# rev_l_v8.net
KiCad netlist of a schematic drawn in EAGLE
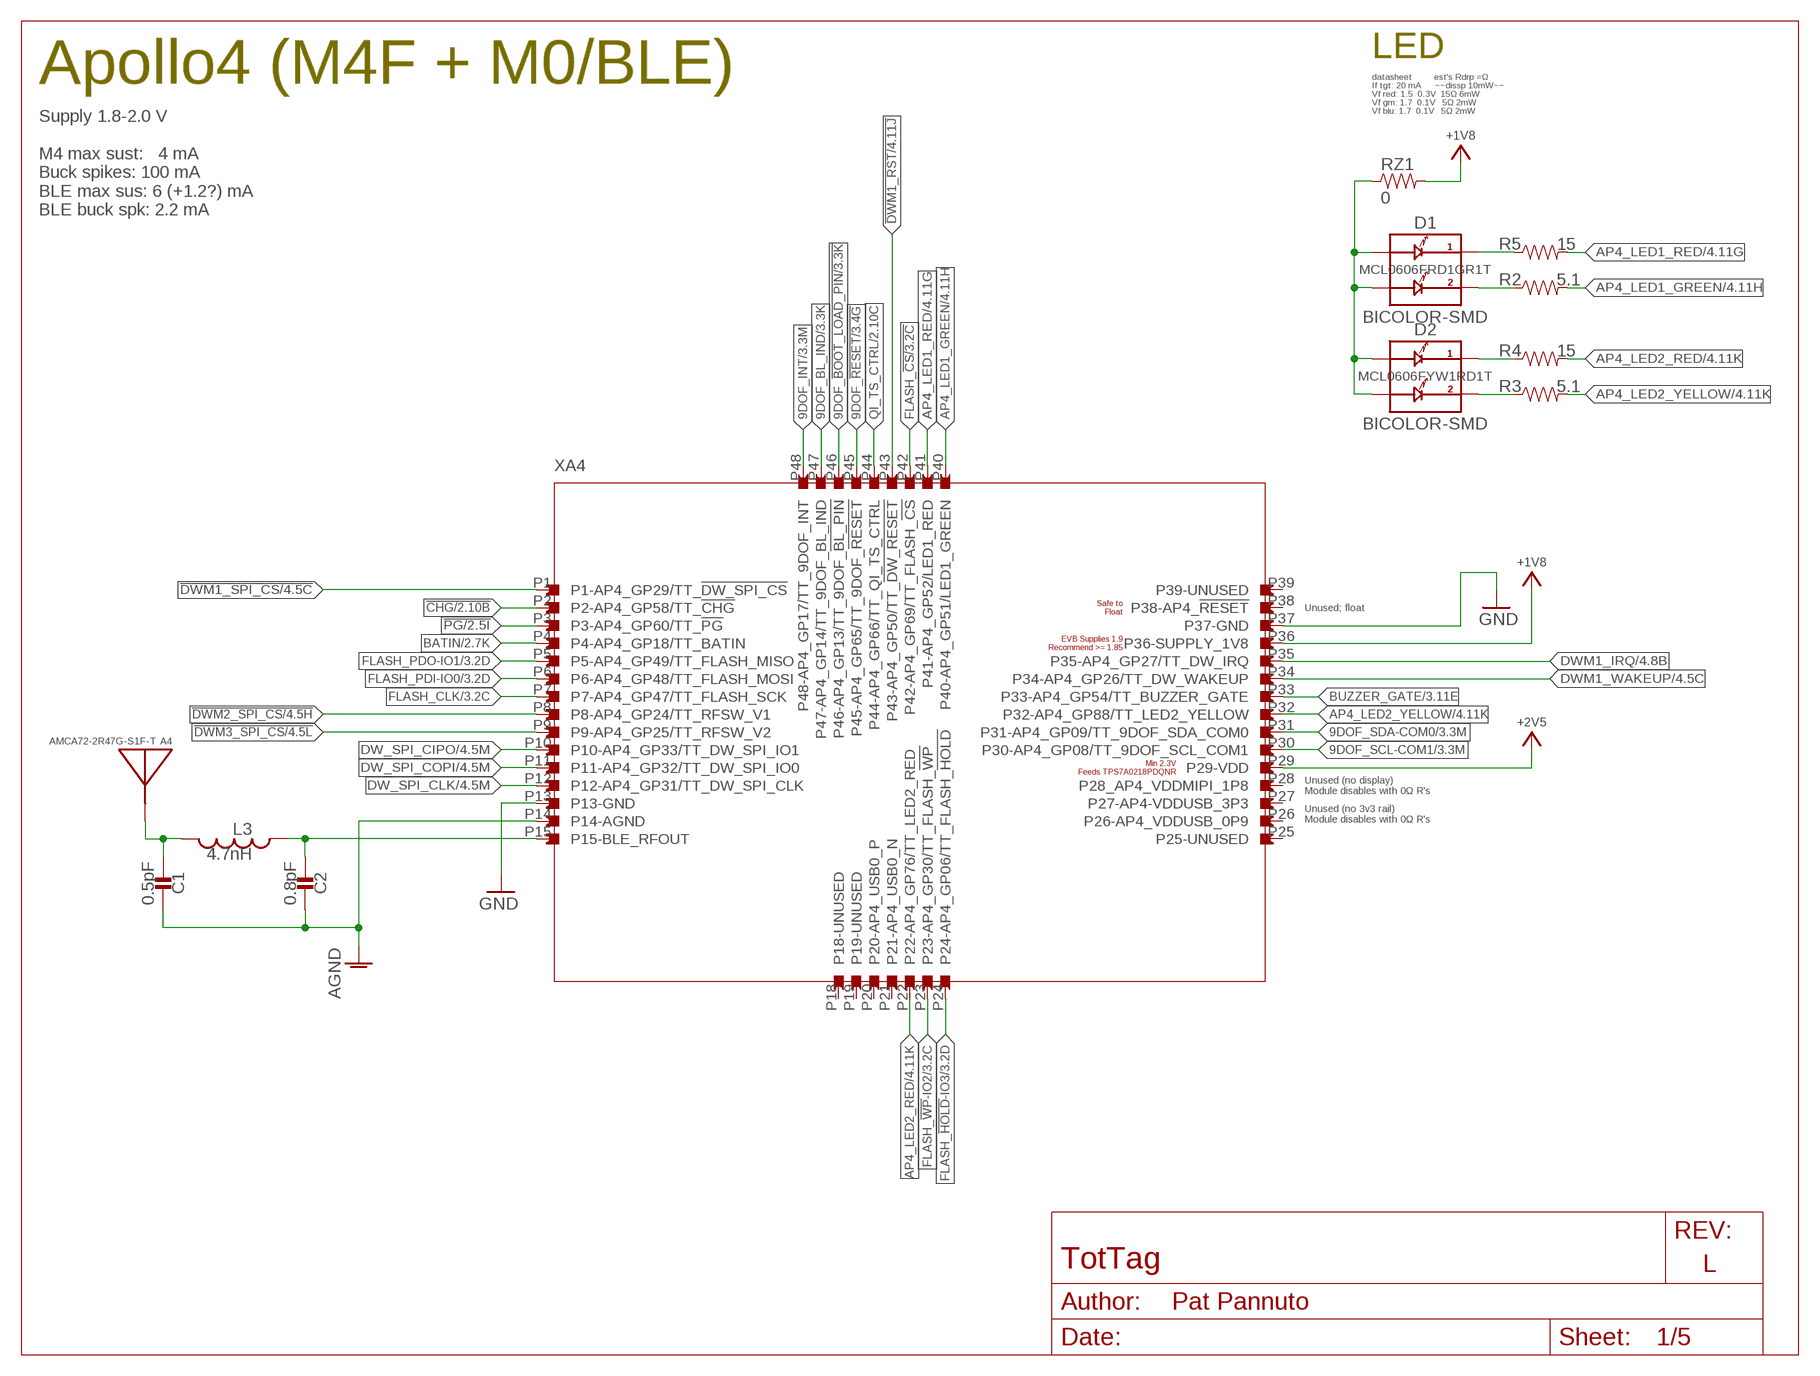
[diagram p0: schematic, sheet 1]
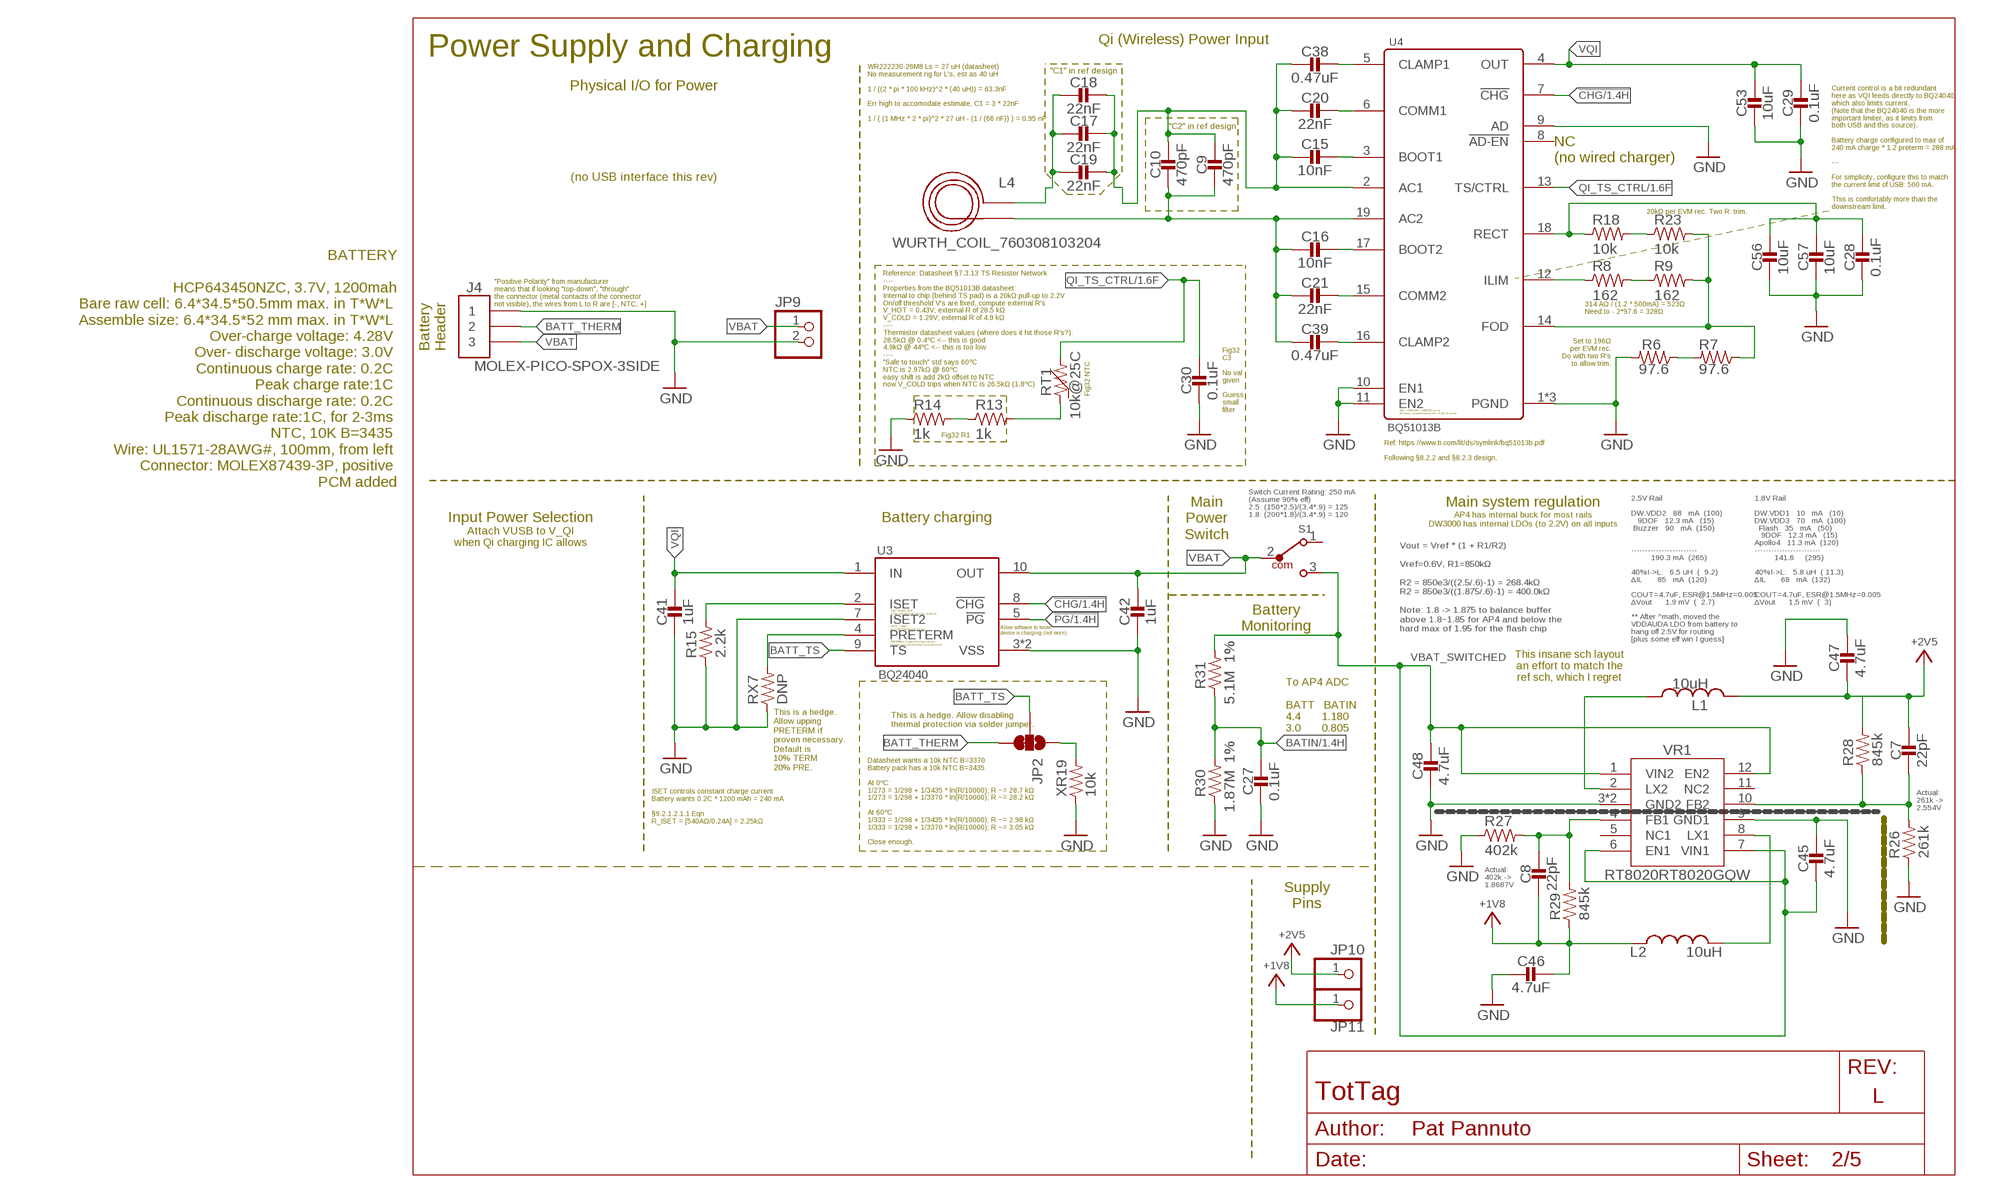
[diagram p1: schematic, sheet 2]
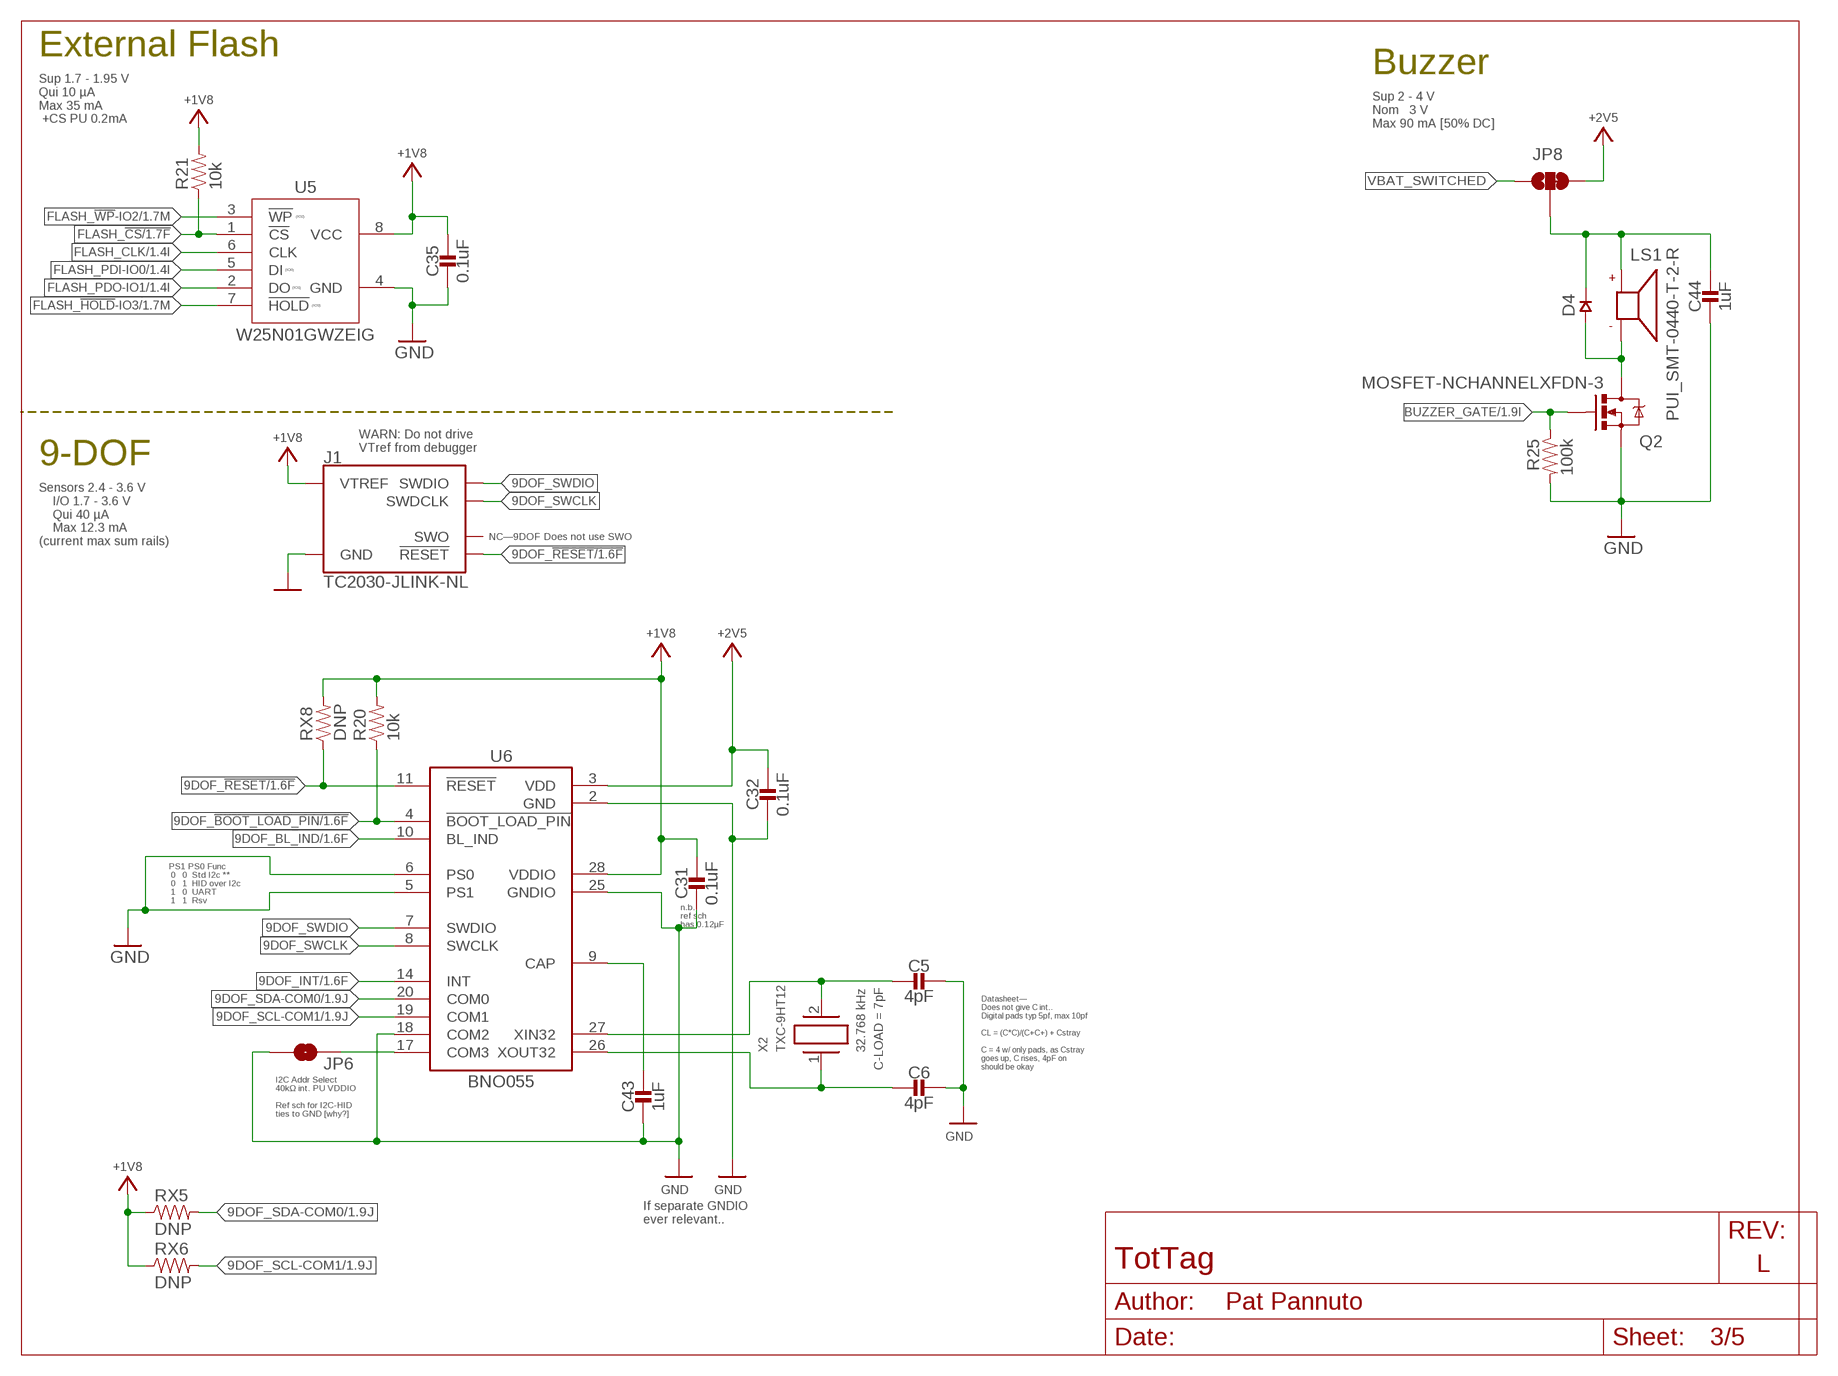
[diagram p2: schematic, sheet 3]
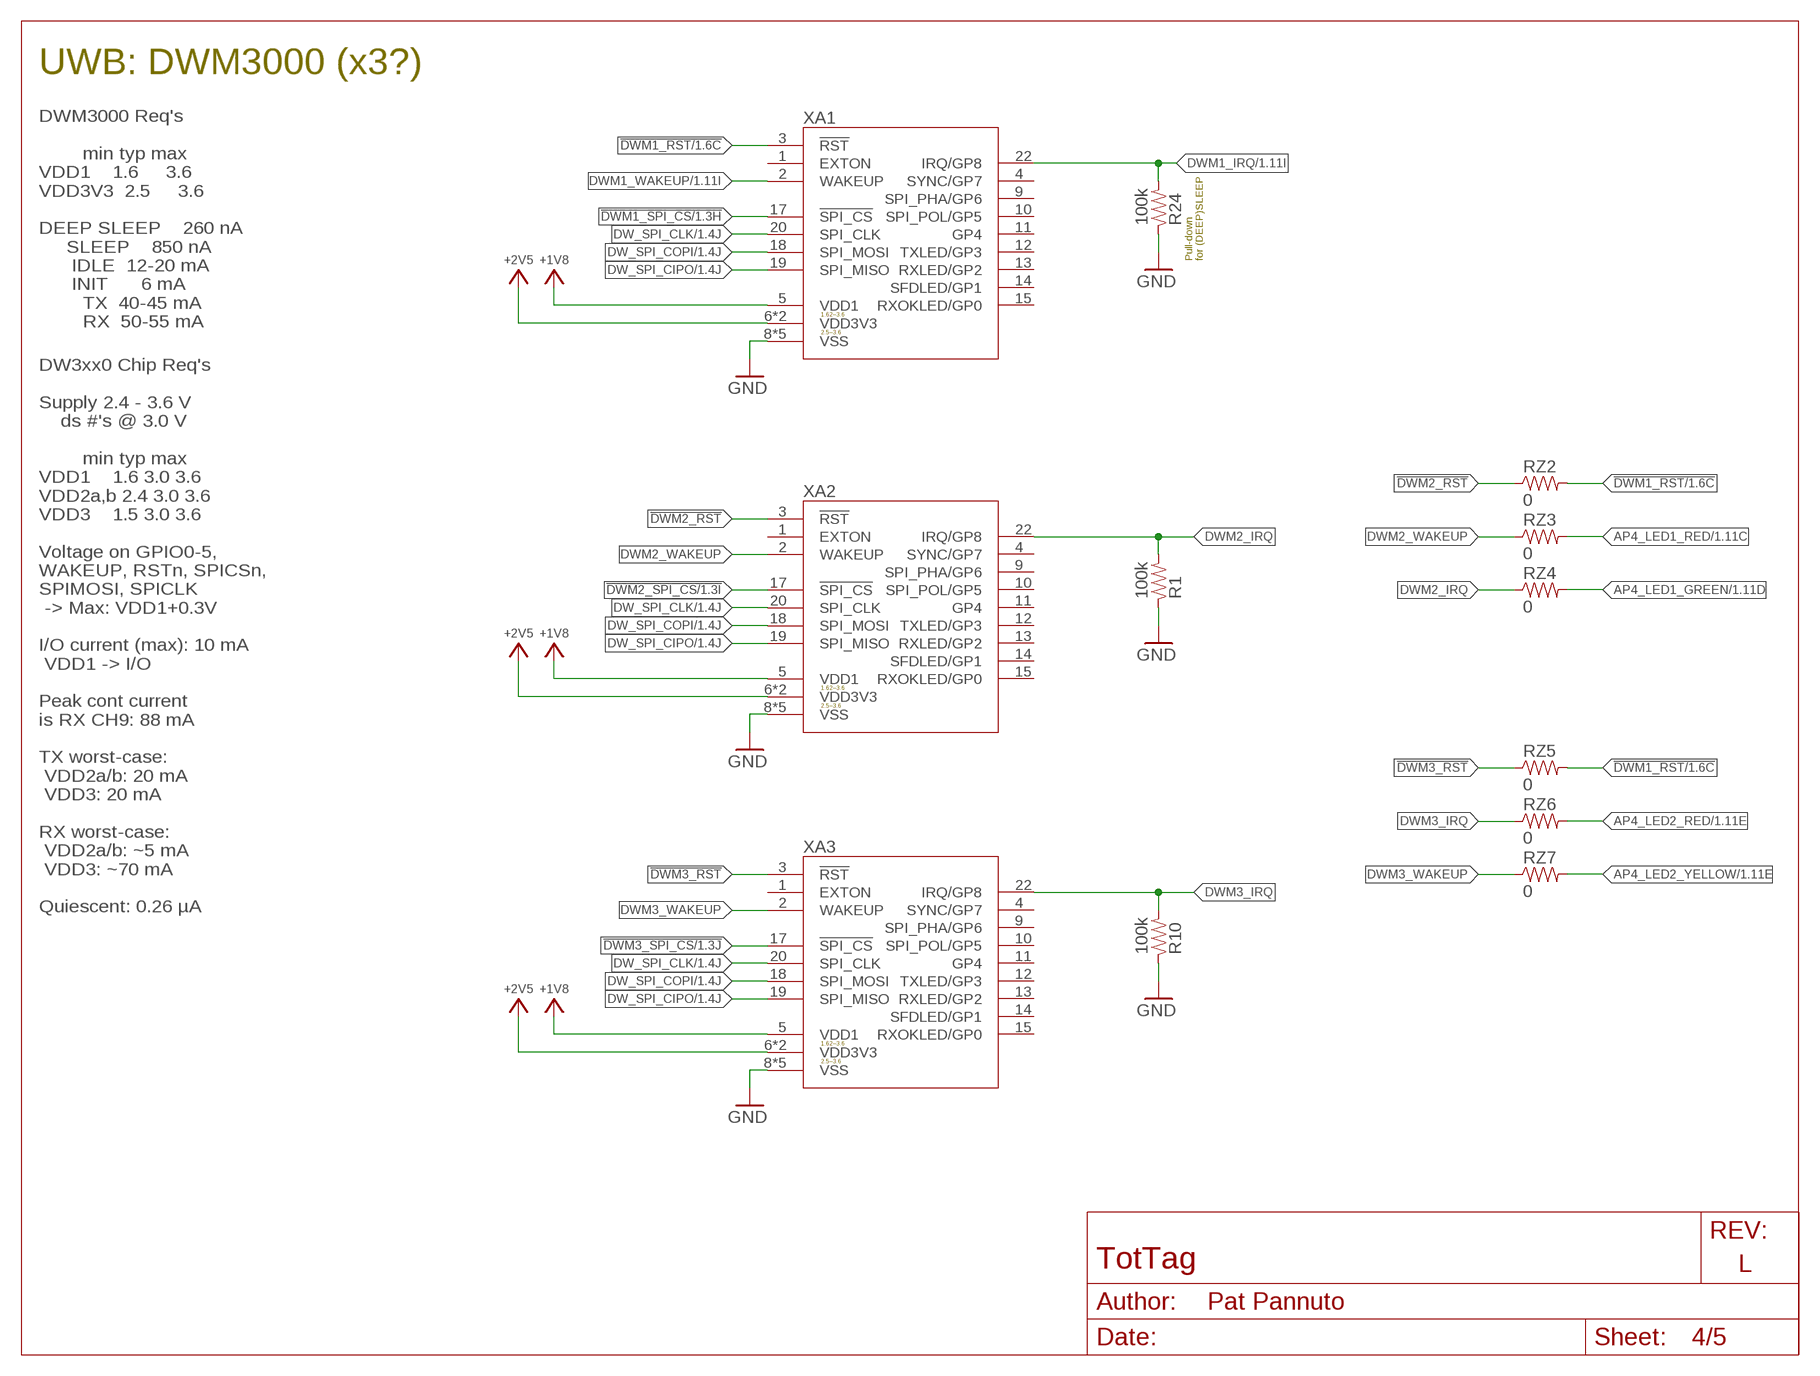
[diagram p3: schematic, sheet 4]
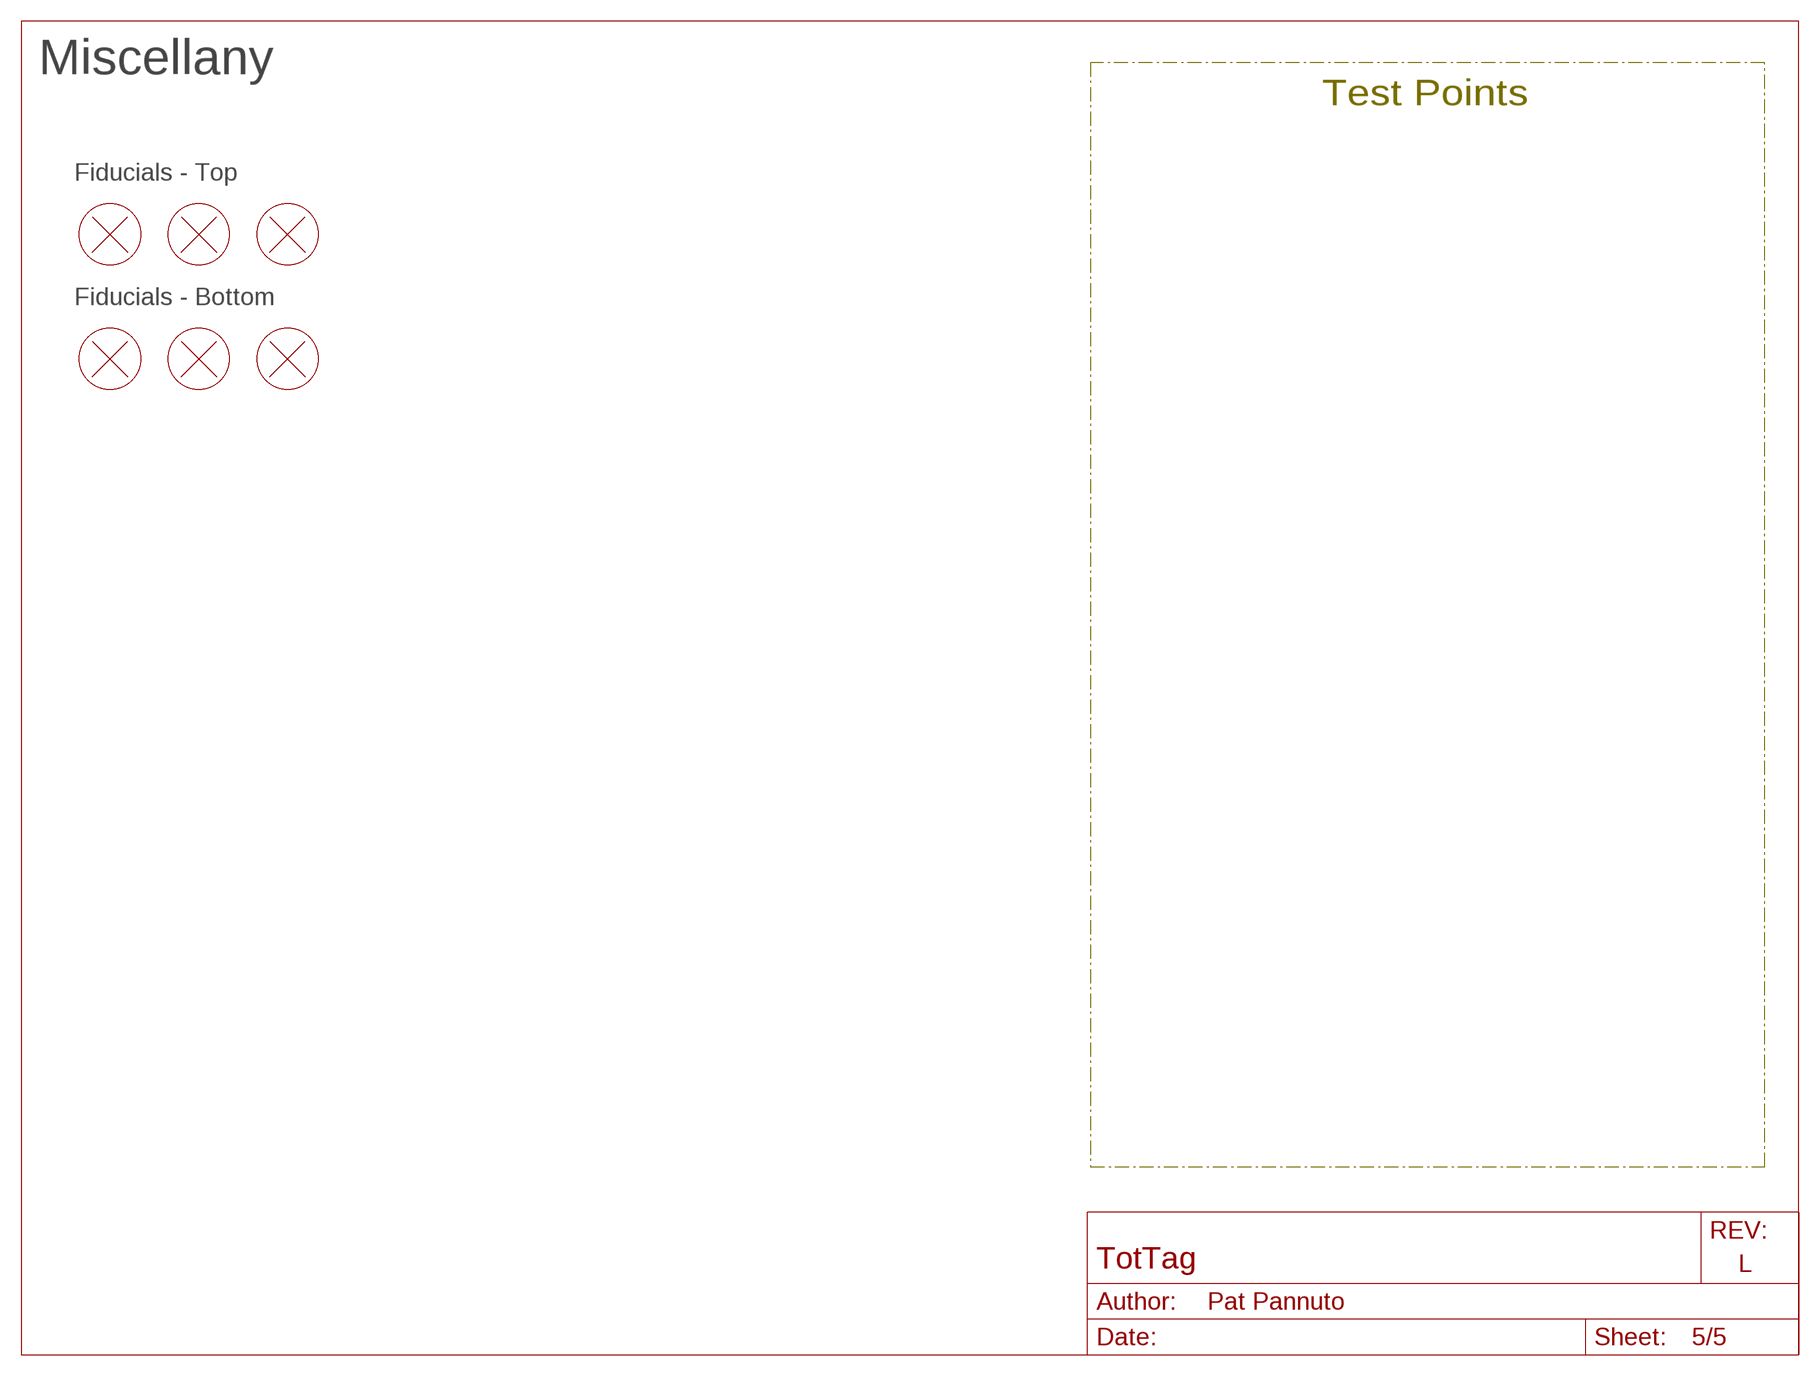
[diagram p4: schematic, sheet 5]

(export (version "E")
  (design (tool "Eeschema 10.0.6"))
  (components
    (comp (ref "R1")
      (value "100k")
      (footprint "eagle-import:0402_RES")
      (fields (field (name "MPN") "RT0402BRE07100KL"))
      (libsource (lib "eagle-import") (part "RESISTOR0402_RES"))
    )
    (comp (ref "R10")
      (value "100k")
      (footprint "eagle-import:0402_RES")
      (fields (field (name "MPN") "RT0402BRE07100KL"))
      (libsource (lib "eagle-import") (part "RESISTOR0402_RES"))
    )
    (comp (ref "R24")
      (value "100k")
      (footprint "eagle-import:0402_RES")
      (fields (field (name "MPN") "RT0402BRE07100KL"))
      (libsource (lib "eagle-import") (part "RESISTOR0402_RES"))
    )
    (comp (ref "RZ2")
      (value "0")
      (footprint "eagle-import:0603-RES")
      (fields (field (name "MPN") "RMCF0603ZT0R00"))
      (libsource (lib "eagle-import") (part "passives_20904581_RESISTOR0603_RES"))
    )
    (comp (ref "RZ3")
      (value "0")
      (footprint "eagle-import:0603-RES")
      (fields (field (name "MPN") "RMCF0603ZT0R00"))
      (libsource (lib "eagle-import") (part "passives_20904581_RESISTOR0603_RES"))
    )
    (comp (ref "RZ4")
      (value "0")
      (footprint "eagle-import:0603-RES")
      (fields (field (name "MPN") "RMCF0603ZT0R00"))
      (libsource (lib "eagle-import") (part "passives_20904581_RESISTOR0603_RES"))
    )
    (comp (ref "RZ5")
      (value "0")
      (footprint "eagle-import:0603-RES")
      (fields (field (name "MPN") "RMCF0603ZT0R00"))
      (libsource (lib "eagle-import") (part "passives_20904581_RESISTOR0603_RES"))
    )
    (comp (ref "RZ6")
      (value "0")
      (footprint "eagle-import:0603-RES")
      (fields (field (name "MPN") "RMCF0603ZT0R00"))
      (libsource (lib "eagle-import") (part "passives_20904581_RESISTOR0603_RES"))
    )
    (comp (ref "RZ7")
      (value "0")
      (footprint "eagle-import:0603-RES")
      (fields (field (name "MPN") "RMCF0603ZT0R00"))
      (libsource (lib "eagle-import") (part "passives_20904581_RESISTOR0603_RES"))
    )
    (comp (ref "XA1")
      (value "DWM3000")
      (footprint "eagle-import:DWM3000")
      (libsource (lib "eagle-import") (part "DWM3000"))
    )
    (comp (ref "XA2")
      (value "DWM3000")
      (footprint "eagle-import:DWM3000")
      (libsource (lib "eagle-import") (part "DWM3000"))
    )
    (comp (ref "XA3")
      (value "DWM3000")
      (footprint "eagle-import:DWM3000")
      (libsource (lib "eagle-import") (part "DWM3000"))
    )
    (comp (ref "C5")
      (value "4pF")
      (footprint "eagle-import:0201_CAP")
      (fields (field (name "MANUFACTURER") "Murata") (field (name "MPN") "GRM0335C1H4R0BA01D"))
      (libsource (lib "eagle-import") (part "passives_20904581_CAPACITOR0201_CAP"))
    )
    (comp (ref "C6")
      (value "4pF")
      (footprint "eagle-import:0201_CAP")
      (fields (field (name "MANUFACTURER") "Murata") (field (name "MPN") "GRM0335C1H4R0BA01D"))
      (libsource (lib "eagle-import") (part "passives_20904581_CAPACITOR0201_CAP"))
    )
    (comp (ref "C31")
      (value "0.1uF")
      (footprint "eagle-import:0402_CAP")
      (fields (field (name "MPN") "CL05A104KP5NNNC"))
      (libsource (lib "eagle-import") (part "passives_20904581_CAPACITOR0402_CAP"))
    )
    (comp (ref "C32")
      (value "0.1uF")
      (footprint "eagle-import:0402_CAP")
      (fields (field (name "MPN") "CL05A104KP5NNNC"))
      (libsource (lib "eagle-import") (part "passives_20904581_CAPACITOR0402_CAP"))
    )
    (comp (ref "C35")
      (value "0.1uF")
      (footprint "eagle-import:0402_CAP")
      (fields (field (name "MPN") "CL05A104KP5NNNC"))
      (libsource (lib "eagle-import") (part "passives_20904581_CAPACITOR0402_CAP"))
    )
    (comp (ref "C43")
      (value "1uF")
      (footprint "eagle-import:0402_CAP")
      (fields (field (name "MPN") "GRM155R70J105KA12J"))
      (libsource (lib "eagle-import") (part "CAPACITOR0402_CAP"))
    )
    (comp (ref "C44")
      (value "1uF")
      (footprint "eagle-import:0402_CAP")
      (fields (field (name "MPN") "GRM155R70J105KA12J"))
      (libsource (lib "eagle-import") (part "CAPACITOR0402_CAP"))
    )
    (comp (ref "D4")
      (value "DIODE0402")
      (footprint "eagle-import:0402_DIODE")
      (fields (field (name "MPN") "CDSQR400B-HF"))
      (libsource (lib "eagle-import") (part "DIODE0402"))
    )
    (comp (ref "J1")
      (value "TC2030-JLINK-NL")
      (footprint "eagle-import:TC2030-IDC-NL")
      (libsource (lib "eagle-import") (part "TC2030-JLINK-NL"))
    )
    (comp (ref "JP6")
      (value "JUMPER-SMT_2_NO_SILK")
      (footprint "eagle-import:SMT-JUMPER_2_NO_SILK")
      (libsource (lib "eagle-import") (part "JUMPER-SMT_2_NO_SILK"))
    )
    (comp (ref "JP8")
      (value "JUMPER-SMT_3_1-NC_TRACE_SILK")
      (footprint "eagle-import:SMT-JUMPER_3_1-NC_TRACE_SILK")
      (libsource (lib "eagle-import") (part "JUMPER-SMT_3_1-NC_TRACE_SILK"))
    )
    (comp (ref "LS1")
      (value "PUI_SMT-0440-T-2-R")
      (footprint "eagle-import:SMT-0440-T-2-R")
      (fields (field (name "MPN") "SMT-0440-T-2-R"))
      (libsource (lib "eagle-import") (part "PUI_SMT-0440-T-2-R"))
    )
    (comp (ref "Q2")
      (value "MOSFET-NCHANNELXFDN-3")
      (footprint "eagle-import:XFDFN-3")
      (libsource (lib "eagle-import") (part "MOSFET-NCHANNELXFDN-3"))
    )
    (comp (ref "R20")
      (value "10k")
      (footprint "eagle-import:0402_RES")
      (fields (field (name "MPN") "RC0402JR-0710KL"))
      (libsource (lib "eagle-import") (part "RESISTOR0402_RES"))
    )
    (comp (ref "R21")
      (value "10k")
      (footprint "eagle-import:0402_RES")
      (fields (field (name "MPN") "RC0402JR-0710KL"))
      (libsource (lib "eagle-import") (part "RESISTOR0402_RES"))
    )
    (comp (ref "R25")
      (value "100k")
      (footprint "eagle-import:0402_RES")
      (fields (field (name "MPN") "RT0402BRE07100KL"))
      (libsource (lib "eagle-import") (part "RESISTOR0402_RES"))
    )
    (comp (ref "RX5")
      (value "DNP")
      (footprint "eagle-import:0603-RES")
      (libsource (lib "eagle-import") (part "passives_20904581_RESISTOR0603_RES"))
    )
    (comp (ref "RX6")
      (value "DNP")
      (footprint "eagle-import:0603-RES")
      (libsource (lib "eagle-import") (part "passives_20904581_RESISTOR0603_RES"))
    )
    (comp (ref "RX8")
      (value "DNP")
      (footprint "eagle-import:0603-RES")
      (libsource (lib "eagle-import") (part "passives_20904581_RESISTOR0603_RES"))
    )
    (comp (ref "U5")
      (value "W25N01GWZEIG")
      (footprint "eagle-import:WSON127P800X600X80-9T430X340N")
      (fields (field (name "MANUFACTURER") "Winbond"))
      (libsource (lib "eagle-import") (part "W25N01GWZEIG"))
    )
    (comp (ref "U6")
      (value "BNO055")
      (footprint "eagle-import:LGA28R0P510X4_5P2X3P8X1")
      (fields (field (name "MANUFACTURER") "Bosch Scientific"))
      (libsource (lib "eagle-import") (part "BNO055"))
    )
    (comp (ref "X2")
      (value "TXC-9HT12")
      (footprint "eagle-import:TXC-9HT12")
      (fields
        (field (name "C-LOAD") "7pF")
        (field (name "FREQUENCY") "32.768 kHz")
        (field (name "MANUFACTURER") "TXC Corp")
        (field (name "MPN") "9HT12-32.768KDZY-T")
      )
      (libsource (lib "eagle-import") (part "TXC-9HT12"))
    )
    (comp (ref "C7")
      (value "22pF")
      (footprint "eagle-import:0201_CAP")
      (fields (field (name "MPN") "GRM0335C1H220FA01D"))
      (libsource (lib "eagle-import") (part "passives_20904581_CAPACITOR0201_CAP"))
    )
    (comp (ref "C8")
      (value "22pF")
      (footprint "eagle-import:0201_CAP")
      (fields (field (name "MPN") "GRM0335C1H220FA01D"))
      (libsource (lib "eagle-import") (part "passives_20904581_CAPACITOR0201_CAP"))
    )
    (comp (ref "C9")
      (value "470pF")
      (footprint "eagle-import:0402_CAP")
      (description "CAP CER 470PF 50V C0G/NP0 0402")
      (fields (field (name "MANUFACTURER") "Murata") (field (name "MPN") "GRM1555C1H471JA01J"))
      (libsource (lib "eagle-import") (part "passives_20904581_CAPACITOR0402_CAP"))
    )
    (comp (ref "C10")
      (value "470pF")
      (footprint "eagle-import:0402_CAP")
      (description "CAP CER 470PF 50V C0G/NP0 0402")
      (fields (field (name "MANUFACTURER") "Murata") (field (name "MPN") "GRM1555C1H471JA01J"))
      (libsource (lib "eagle-import") (part "passives_20904581_CAPACITOR0402_CAP"))
    )
    (comp (ref "C15")
      (value "10nF")
      (footprint "eagle-import:0402_CAP")
      (fields (field (name "MPN") "GRM155R71H103KA88J"))
      (libsource (lib "eagle-import") (part "passives_20904581_CAPACITOR0402_CAP"))
    )
    (comp (ref "C16")
      (value "10nF")
      (footprint "eagle-import:0402_CAP")
      (fields (field (name "MPN") "GRM155R71H103KA88J"))
      (libsource (lib "eagle-import") (part "passives_20904581_CAPACITOR0402_CAP"))
    )
    (comp (ref "C17")
      (value "22nF")
      (footprint "eagle-import:0402_CAP")
      (fields (field (name "MPN") "GRM155R71E223JA61D"))
      (libsource (lib "eagle-import") (part "passives_20904581_CAPACITOR0402_CAP"))
    )
    (comp (ref "C18")
      (value "22nF")
      (footprint "eagle-import:0402_CAP")
      (fields (field (name "MPN") "GRM155R71E223JA61D"))
      (libsource (lib "eagle-import") (part "passives_20904581_CAPACITOR0402_CAP"))
    )
    (comp (ref "C19")
      (value "22nF")
      (footprint "eagle-import:0402_CAP")
      (fields (field (name "MPN") "GRM155R71E223JA61D"))
      (libsource (lib "eagle-import") (part "passives_20904581_CAPACITOR0402_CAP"))
    )
    (comp (ref "C20")
      (value "22nF")
      (footprint "eagle-import:0402_CAP")
      (fields (field (name "MPN") "CC0402ZRY5V8BB223"))
      (libsource (lib "eagle-import") (part "passives_20904581_CAPACITOR0402_CAP"))
    )
    (comp (ref "C21")
      (value "22nF")
      (footprint "eagle-import:0402_CAP")
      (fields (field (name "MPN") "CC0402ZRY5V8BB223"))
      (libsource (lib "eagle-import") (part "passives_20904581_CAPACITOR0402_CAP"))
    )
    (comp (ref "C27")
      (value "0.1uF")
      (footprint "eagle-import:0402_CAP")
      (fields (field (name "MPN") "GRM155R71C104KA88J "))
      (libsource (lib "eagle-import") (part "CAPACITOR0402_CAP"))
    )
    (comp (ref "C28")
      (value "0.1uF")
      (footprint "eagle-import:0402_CAP")
      (fields (field (name "MPN") "GRM155R71C104KA88J "))
      (libsource (lib "eagle-import") (part "CAPACITOR0402_CAP"))
    )
    (comp (ref "C29")
      (value "0.1uF")
      (footprint "eagle-import:0402_CAP")
      (fields (field (name "MPN") "GRM155R71C104KA88J "))
      (libsource (lib "eagle-import") (part "CAPACITOR0402_CAP"))
    )
    (comp (ref "C30")
      (value "0.1uF")
      (footprint "eagle-import:0402_CAP")
      (fields (field (name "MPN") "GRM155R71C104KA88J "))
      (libsource (lib "eagle-import") (part "CAPACITOR0402_CAP"))
    )
    (comp (ref "C38")
      (value "0.47uF")
      (footprint "eagle-import:0402_CAP")
      (fields (field (name "MPN") "GRT155R61E474ME01D"))
      (libsource (lib "eagle-import") (part "passives_20904581_CAPACITOR0402_CAP"))
    )
    (comp (ref "C39")
      (value "0.47uF")
      (footprint "eagle-import:0402_CAP")
      (fields (field (name "MPN") "GRT155R61E474ME01D"))
      (libsource (lib "eagle-import") (part "passives_20904581_CAPACITOR0402_CAP"))
    )
    (comp (ref "C41")
      (value "1uF")
      (footprint "eagle-import:0402_CAP")
      (fields (field (name "MPN") "GRM155R70J105KA12J"))
      (libsource (lib "eagle-import") (part "CAPACITOR0402_CAP"))
    )
    (comp (ref "C42")
      (value "1uF")
      (footprint "eagle-import:0402_CAP")
      (fields (field (name "MPN") "GRM155R70J105KA12J"))
      (libsource (lib "eagle-import") (part "CAPACITOR0402_CAP"))
    )
    (comp (ref "C45")
      (value "4.7uF")
      (footprint "eagle-import:0603_CAP")
      (fields (field (name "MPN") "C1608X7S1A475K080AC"))
      (libsource (lib "eagle-import") (part "passives_20904581_CAPACITOR0603_CAP"))
    )
    (comp (ref "C46")
      (value "4.7uF")
      (footprint "eagle-import:0603_CAP")
      (fields (field (name "MPN") "C1608X7S1A475K080AC"))
      (libsource (lib "eagle-import") (part "passives_20904581_CAPACITOR0603_CAP"))
    )
    (comp (ref "C47")
      (value "4.7uF")
      (footprint "eagle-import:0603_CAP")
      (fields (field (name "MPN") "C1608X7S1A475K080AC"))
      (libsource (lib "eagle-import") (part "passives_20904581_CAPACITOR0603_CAP"))
    )
    (comp (ref "C48")
      (value "4.7uF")
      (footprint "eagle-import:0603_CAP")
      (fields (field (name "MPN") "C1608X7S1A475K080AC"))
      (libsource (lib "eagle-import") (part "passives_20904581_CAPACITOR0603_CAP"))
    )
    (comp (ref "C53")
      (value "10uF")
      (footprint "eagle-import:0603_CAP")
      (fields (field (name "MPN") "CM105X5R106M25AT"))
      (libsource (lib "eagle-import") (part "passives_20904581_CAPACITOR0603_CAP"))
    )
    (comp (ref "C56")
      (value "10uF")
      (footprint "eagle-import:0603_CAP")
      (fields (field (name "MPN") "CM105X5R106M25AT"))
      (libsource (lib "eagle-import") (part "passives_20904581_CAPACITOR0603_CAP"))
    )
    (comp (ref "C57")
      (value "10uF")
      (footprint "eagle-import:0603_CAP")
      (fields (field (name "MPN") "CM105X5R106M25AT"))
      (libsource (lib "eagle-import") (part "passives_20904581_CAPACITOR0603_CAP"))
    )
    (comp (ref "J4")
      (value "MOLEX-PICO-SPOX-3SIDE")
      (footprint "eagle-import:MOLEX-PICO-SPOX-3_SIDE")
      (libsource (lib "eagle-import") (part "MOLEX-PICO-SPOX-3SIDE"))
    )
    (comp (ref "JP2")
      (value "JUMPER-SMT_3_1-NC_TRACE_SILK")
      (footprint "eagle-import:SMT-JUMPER_3_1-NC_TRACE_SILK")
      (libsource (lib "eagle-import") (part "JUMPER-SMT_3_1-NC_TRACE_SILK"))
    )
    (comp (ref "JP9")
      (value "PINHD-1X2")
      (footprint "eagle-import:1X02")
      (libsource (lib "eagle-import") (part "PINHD-1X2"))
    )
    (comp (ref "JP10")
      (value "PINHD-1X1")
      (footprint "eagle-import:1X01")
      (libsource (lib "eagle-import") (part "PINHD-1X1"))
    )
    (comp (ref "JP11")
      (value "PINHD-1X1")
      (footprint "eagle-import:1X01")
      (libsource (lib "eagle-import") (part "PINHD-1X1"))
    )
    (comp (ref "L1")
      (value "10uH")
      (footprint "eagle-import:NRX3015")
      (fields (field (name "MANUFACTURER") "TAIYO YUDEN") (field (name "MPN") "NR3015T100M"))
      (libsource (lib "eagle-import") (part "INDUCTORNRX3015"))
    )
    (comp (ref "L2")
      (value "10uH")
      (footprint "eagle-import:NRX3015")
      (fields (field (name "MANUFACTURER") "TAIYO YUDEN") (field (name "MPN") "NR3015T100M"))
      (libsource (lib "eagle-import") (part "INDUCTORNRX3015"))
    )
    (comp (ref "L4")
      (value "WURTH_COIL_760308103204")
      (footprint "eagle-import:WURTH_COIL_760308103204")
      (fields (field (name "MANUFACTURER") "Würth Elektronik") (field (name "MPN") "760308103204"))
      (libsource (lib "eagle-import") (part "WURTH_COIL_760308103204"))
    )
    (comp (ref "R6")
      (value "97.6")
      (footprint "eagle-import:0402_RES")
      (fields (field (name "MPN") "RMCF0402FT97R6"))
      (libsource (lib "eagle-import") (part "passives_20904581_RESISTOR0402_RES"))
    )
    (comp (ref "R7")
      (value "97.6")
      (footprint "eagle-import:0402_RES")
      (fields (field (name "MPN") "RMCF0402FT97R6"))
      (libsource (lib "eagle-import") (part "passives_20904581_RESISTOR0402_RES"))
    )
    (comp (ref "R8")
      (value "162")
      (footprint "eagle-import:0402_RES")
      (fields (field (name "MPN") "RMCF0402FT162R"))
      (libsource (lib "eagle-import") (part "passives_20904581_RESISTOR0402_RES"))
    )
    (comp (ref "R9")
      (value "162")
      (footprint "eagle-import:0402_RES")
      (fields (field (name "MPN") "RMCF0402FT162R"))
      (libsource (lib "eagle-import") (part "passives_20904581_RESISTOR0402_RES"))
    )
    (comp (ref "R13")
      (value "1k")
      (footprint "eagle-import:0402_RES")
      (libsource (lib "eagle-import") (part "RESISTOR0402_RES"))
    )
    (comp (ref "R14")
      (value "1k")
      (footprint "eagle-import:0402_RES")
      (libsource (lib "eagle-import") (part "RESISTOR0402_RES"))
    )
    (comp (ref "R15")
      (value "2.2k")
      (footprint "eagle-import:0402_RES")
      (fields (field (name "MPN") "RMCF0402JT2K20"))
      (libsource (lib "eagle-import") (part "passives_20904581_RESISTOR0402_RES"))
    )
    (comp (ref "R18")
      (value "10k")
      (footprint "eagle-import:0402_RES")
      (fields (field (name "MPN") "RC0402JR-0710KL"))
      (libsource (lib "eagle-import") (part "RESISTOR0402_RES"))
    )
    (comp (ref "R23")
      (value "10k")
      (footprint "eagle-import:0402_RES")
      (fields (field (name "MPN") "RC0402JR-0710KL"))
      (libsource (lib "eagle-import") (part "RESISTOR0402_RES"))
    )
    (comp (ref "R26")
      (value "261k")
      (footprint "eagle-import:0201_RES")
      (fields (field (name "MPN") "ERJ-1GNF2613C"))
      (libsource (lib "eagle-import") (part "passives_20904581_RESISTOR0201_RES"))
    )
    (comp (ref "R27")
      (value "402k")
      (footprint "eagle-import:0201_RES")
      (fields (field (name "MPN") "ERJ-1GNF4023C"))
      (libsource (lib "eagle-import") (part "passives_20904581_RESISTOR0201_RES"))
    )
    (comp (ref "R28")
      (value "845k")
      (footprint "eagle-import:0201_RES")
      (fields (field (name "MPN") "ERJ-1GNF8453C"))
      (libsource (lib "eagle-import") (part "passives_20904581_RESISTOR0201_RES"))
    )
    (comp (ref "R29")
      (value "845k")
      (footprint "eagle-import:0201_RES")
      (fields (field (name "MPN") "ERJ-1GNF8453C"))
      (libsource (lib "eagle-import") (part "passives_20904581_RESISTOR0201_RES"))
    )
    (comp (ref "R30")
      (value "1.87M")
      (footprint "eagle-import:0402_RES")
      (fields (field (name "MPN") "RMCF0402FT1M87") (field (name "TOLERANCE") "1%"))
      (libsource (lib "eagle-import") (part "RESISTOR0402_RES"))
    )
    (comp (ref "R31")
      (value "5.1M")
      (footprint "eagle-import:0402_RES")
      (fields (field (name "MPN") "RMCF0402FT5M10") (field (name "TOLERANCE") "1%"))
      (libsource (lib "eagle-import") (part "RESISTOR0402_RES"))
    )
    (comp (ref "RT1")
      (value "10k@25C")
      (footprint "eagle-import:0402_RES")
      (fields (field (name "MPN") "NCU15XH103F60RC"))
      (libsource (lib "eagle-import") (part "THERMISTOR0402"))
    )
    (comp (ref "RX7")
      (value "DNP")
      (footprint "eagle-import:0402_RES")
      (libsource (lib "eagle-import") (part "passives_20904581_RESISTOR0402_RES"))
    )
    (comp (ref "S1")
      (value "450404015514")
      (footprint "eagle-import:450404015514")
      (libsource (lib "eagle-import") (part "450404015514"))
    )
    (comp (ref "U3")
      (value "BQ24040")
      (footprint "eagle-import:DSQ0010A")
      (fields (field (name "MPN") "BQ24040DSQR"))
      (libsource (lib "eagle-import") (part "BQ24040"))
    )
    (comp (ref "U4")
      (value "BQ51013B")
      (footprint "eagle-import:RHL0020A")
      (fields (field (name "MPN") "BQ51013BRHLR"))
      (libsource (lib "eagle-import") (part "BQ51013B"))
    )
    (comp (ref "VR1")
      (value "RT8020RT8020GQW")
      (footprint "eagle-import:SON45P300X300X80-13T160X250N")
      (fields (field (name "MANUFACTURER") "RichTek") (field (name "MPN") "RT8020GQW"))
      (libsource (lib "eagle-import") (part "RT8020RT8020GQW"))
    )
    (comp (ref "XR19")
      (value "10k")
      (footprint "eagle-import:0402_RES")
      (fields (field (name "MPN") "RC0402JR-0710KL"))
      (libsource (lib "eagle-import") (part "RESISTOR0402_RES"))
    )
    (comp (ref "A4")
      (value "AMCA72-2R47G-S1F-T")
      (footprint "eagle-import:AMCA72-2R470G-S1F-T")
      (fields (field (name "MPN") "AMCA72-2R470G-S1F-T4"))
      (libsource (lib "eagle-import") (part "AMCA72-2R47G-S1F-T"))
    )
    (comp (ref "C1")
      (value "0.5pF")
      (footprint "eagle-import:0402_CAP")
      (fields (field (name "MPN") "GJM1555C1HR50WB01D"))
      (libsource (lib "eagle-import") (part "CAPACITOR0402_CAP"))
    )
    (comp (ref "C2")
      (value "0.8pF")
      (footprint "eagle-import:0402_CAP")
      (fields (field (name "MPN") "GJM1555C1HR80WB01D"))
      (libsource (lib "eagle-import") (part "CAPACITOR0402_CAP"))
    )
    (comp (ref "D1")
      (value "BICOLOR-SMD")
      (footprint "eagle-import:LED-0606")
      (fields (field (name "MPN") "MCL0606FRD1GR1T"))
      (libsource (lib "eagle-import") (part "BICOLOR-SMD"))
    )
    (comp (ref "D2")
      (value "BICOLOR-SMD")
      (footprint "eagle-import:LED-0606")
      (fields (field (name "MPN") "MCL0606FYW1RD1T"))
      (libsource (lib "eagle-import") (part "BICOLOR-SMD"))
    )
    (comp (ref "L3")
      (value "4.7nH")
      (footprint "eagle-import:0402_CAP")
      (fields (field (name "MPN") "LQW15AN4N7G8ZD"))
      (libsource (lib "eagle-import") (part "INDUCTOR0402"))
    )
    (comp (ref "R2")
      (value "5.1")
      (footprint "eagle-import:0402_RES")
      (fields (field (name "MPN") "RC0402JR-075R1L"))
      (libsource (lib "eagle-import") (part "RESISTOR0402_RES"))
    )
    (comp (ref "R3")
      (value "5.1")
      (footprint "eagle-import:0402_RES")
      (fields (field (name "MPN") "RC0402JR-075R1L"))
      (libsource (lib "eagle-import") (part "RESISTOR0402_RES"))
    )
    (comp (ref "R4")
      (value "15")
      (footprint "eagle-import:0402_RES")
      (fields (field (name "MPN") "RC0402JR-0715RL"))
      (libsource (lib "eagle-import") (part "RESISTOR0402_RES"))
    )
    (comp (ref "R5")
      (value "15")
      (footprint "eagle-import:0402_RES")
      (fields (field (name "MPN") "RC0402JR-0715RL"))
      (libsource (lib "eagle-import") (part "RESISTOR0402_RES"))
    )
    (comp (ref "RZ1")
      (value "0")
      (footprint "eagle-import:0603-RES")
      (fields (field (name "MPN") "RMCF0603ZT0R00"))
      (libsource (lib "eagle-import") (part "passives_20904581_RESISTOR0603_RES"))
    )
    (comp (ref "XA4")
      (value "APOLLO4_BLUEPLUS_MODULE")
      (footprint "eagle-import:APOLLO4_BLUEPLUS_MODULE")
      (libsource (lib "eagle-import") (part "APOLLO4_BLUEPLUS_MODULE"))
    )
    (comp (ref "FD1")
      (value "FIDUCIAL")
      (footprint "eagle-import:FIDUCIAL_1MM-CU_2MM-MASK")
      (libsource (lib "eagle-import") (part "FIDUCIAL"))
    )
    (comp (ref "FD2")
      (value "FIDUCIAL")
      (footprint "eagle-import:FIDUCIAL_1MM-CU_2MM-MASK")
      (libsource (lib "eagle-import") (part "FIDUCIAL"))
    )
    (comp (ref "FD3")
      (value "FIDUCIAL")
      (footprint "eagle-import:FIDUCIAL_1MM-CU_2MM-MASK")
      (libsource (lib "eagle-import") (part "FIDUCIAL"))
    )
    (comp (ref "FD4")
      (value "FIDUCIAL")
      (footprint "eagle-import:FIDUCIAL_1MM-CU_2MM-MASK")
      (libsource (lib "eagle-import") (part "FIDUCIAL"))
    )
    (comp (ref "FD5")
      (value "FIDUCIAL")
      (footprint "eagle-import:FIDUCIAL_1MM-CU_2MM-MASK")
      (libsource (lib "eagle-import") (part "FIDUCIAL"))
    )
    (comp (ref "FD6")
      (value "FIDUCIAL")
      (footprint "eagle-import:FIDUCIAL_1MM-CU_2MM-MASK")
      (libsource (lib "eagle-import") (part "FIDUCIAL"))
    )
  )
  (nets
    (net (code "1") (name "+1V8") (class "Default")
      (node (ref "C31") (pin "1") (pinfunction "1_1") (pintype "bidirectional"))
      (node (ref "C35") (pin "1") (pinfunction "1_1") (pintype "bidirectional"))
      (node (ref "C46") (pin "1") (pinfunction "1_1") (pintype "bidirectional"))
      (node (ref "C8") (pin "P$2") (pinfunction "2_P$2") (pintype "bidirectional"))
      (node (ref "J1") (pin "1") (pinfunction "VTREF_1") (pintype "bidirectional"))
      (node (ref "JP11") (pin "1") (pinfunction "1_1") (pintype "passive"))
      (node (ref "L2") (pin "P$1") (pinfunction "1_P$1") (pintype "bidirectional"))
      (node (ref "R20") (pin "2") (pinfunction "2_2") (pintype "passive"))
      (node (ref "R21") (pin "2") (pinfunction "2_2") (pintype "passive"))
      (node (ref "R29") (pin "1") (pinfunction "1_1") (pintype "passive"))
      (node (ref "RX5") (pin "1") (pinfunction "1_1") (pintype "passive"))
      (node (ref "RX6") (pin "1") (pinfunction "1_1") (pintype "passive"))
      (node (ref "RX8") (pin "2") (pinfunction "2_2") (pintype "passive"))
      (node (ref "RZ1") (pin "2") (pinfunction "2_2") (pintype "passive"))
      (node (ref "U5") (pin "8") (pinfunction "VCC_8") (pintype "bidirectional"))
      (node (ref "U6") (pin "28") (pinfunction "VDDIO_28") (pintype "bidirectional"))
      (node (ref "XA1") (pin "5") (pinfunction "VDD1_5") (pintype "bidirectional"))
      (node (ref "XA2") (pin "5") (pinfunction "VDD1_5") (pintype "bidirectional"))
      (node (ref "XA3") (pin "5") (pinfunction "VDD1_5") (pintype "bidirectional"))
      (node (ref "XA4") (pin "P36") (pinfunction "P36-SUPPLY_1V8_P36") (pintype "bidirectional"))
    )
    (net (code "2") (name "+2V5") (class "Default")
      (node (ref "C32") (pin "1") (pinfunction "1_1") (pintype "bidirectional"))
      (node (ref "C47") (pin "2") (pinfunction "2_2") (pintype "bidirectional"))
      (node (ref "C7") (pin "P$1") (pinfunction "1_P$1") (pintype "bidirectional"))
      (node (ref "JP10") (pin "1") (pinfunction "1_1") (pintype "passive"))
      (node (ref "JP8") (pin "3") (pinfunction "3_3") (pintype "passive"))
      (node (ref "L1") (pin "P$2") (pinfunction "2_P$2") (pintype "bidirectional"))
      (node (ref "R28") (pin "2") (pinfunction "2_2") (pintype "passive"))
      (node (ref "U6") (pin "3") (pinfunction "VDD_3") (pintype "bidirectional"))
      (node (ref "XA1") (pin "6") (pinfunction "VDD3V3_6") (pintype "bidirectional"))
      (node (ref "XA1") (pin "7") (pinfunction "VDD3V3_7") (pintype "bidirectional"))
      (node (ref "XA2") (pin "6") (pinfunction "VDD3V3_6") (pintype "bidirectional"))
      (node (ref "XA2") (pin "7") (pinfunction "VDD3V3_7") (pintype "bidirectional"))
      (node (ref "XA3") (pin "6") (pinfunction "VDD3V3_6") (pintype "bidirectional"))
      (node (ref "XA3") (pin "7") (pinfunction "VDD3V3_7") (pintype "bidirectional"))
      (node (ref "XA4") (pin "P29") (pinfunction "P29-VDD_P29") (pintype "bidirectional"))
    )
    (net (code "3") (name "9DOF_BL_IND") (class "Default")
      (node (ref "U6") (pin "10") (pinfunction "BL_IND_10") (pintype "output"))
      (node (ref "XA4") (pin "P47") (pinfunction "P47-AP4_GP14/TT_9DOF_BL_IND_P47") (pintype "bidirectional"))
    )
    (net (code "4") (name "9DOF_INT") (class "Default")
      (node (ref "U6") (pin "14") (pinfunction "INT_14") (pintype "output"))
      (node (ref "XA4") (pin "P48") (pinfunction "P48-AP4_GP17/TT_9DOF_INT_P48") (pintype "bidirectional"))
    )
    (net (code "5") (name "9DOF_SCL-COM1") (class "Default")
      (node (ref "RX6") (pin "2") (pinfunction "2_2") (pintype "passive"))
      (node (ref "U6") (pin "19") (pinfunction "COM1_19") (pintype "bidirectional"))
      (node (ref "XA4") (pin "P30") (pinfunction "P30-AP4_GP08/TT_9DOF_SCL_COM1_P30") (pintype "bidirectional"))
    )
    (net (code "6") (name "9DOF_SDA-COM0") (class "Default")
      (node (ref "RX5") (pin "2") (pinfunction "2_2") (pintype "passive"))
      (node (ref "U6") (pin "20") (pinfunction "COM0_20") (pintype "bidirectional"))
      (node (ref "XA4") (pin "P31") (pinfunction "P31-AP4_GP09/TT_9DOF_SDA_COM0_P31") (pintype "bidirectional"))
    )
    (net (code "7") (name "9DOF_SWCLK") (class "Default")
      (node (ref "J1") (pin "4") (pinfunction "SWDCLK_4") (pintype "bidirectional"))
      (node (ref "U6") (pin "8") (pinfunction "SWCLK_8") (pintype "input"))
    )
    (net (code "8") (name "9DOF_SWDIO") (class "Default")
      (node (ref "J1") (pin "2") (pinfunction "SWDIO_2") (pintype "bidirectional"))
      (node (ref "U6") (pin "7") (pinfunction "SWDIO_7") (pintype "bidirectional"))
    )
    (net (code "9") (name "9DOF_~{BOOT_LOAD_PIN}") (class "Default")
      (node (ref "R20") (pin "1") (pinfunction "1_1") (pintype "passive"))
      (node (ref "U6") (pin "4") (pinfunction "~{BOOT_LOAD_PIN}_4") (pintype "input"))
      (node (ref "XA4") (pin "P46") (pinfunction "P46-AP4_GP13/TT_9DOF_~{BL_PIN}_P46") (pintype "bidirectional"))
    )
    (net (code "10") (name "9DOF_~{RESET}") (class "Default")
      (node (ref "J1") (pin "3") (pinfunction "~{RESET}_3") (pintype "bidirectional"))
      (node (ref "RX8") (pin "1") (pinfunction "1_1") (pintype "passive"))
      (node (ref "U6") (pin "11") (pinfunction "~{RESET}_11") (pintype "bidirectional"))
      (node (ref "XA4") (pin "P45") (pinfunction "P45-AP4_GP65/TT_9DOF_~{RESET}_P45") (pintype "bidirectional"))
    )
    (net (code "11") (name "AGND") (class "Default")
      (node (ref "C1") (pin "2") (pinfunction "2_2") (pintype "bidirectional"))
      (node (ref "C2") (pin "2") (pinfunction "2_2") (pintype "bidirectional"))
      (node (ref "XA4") (pin "P14") (pinfunction "P14-AGND_P14") (pintype "bidirectional"))
    )
    (net (code "12") (name "AP4_LED1_GREEN") (class "Default")
      (node (ref "R2") (pin "2") (pinfunction "2_2") (pintype "passive"))
      (node (ref "RZ4") (pin "2") (pinfunction "2_2") (pintype "passive"))
      (node (ref "XA4") (pin "P40") (pinfunction "P40-AP4_GP51/LED1_GREEN_P40") (pintype "bidirectional"))
    )
    (net (code "13") (name "AP4_LED1_RED") (class "Default")
      (node (ref "R5") (pin "2") (pinfunction "2_2") (pintype "passive"))
      (node (ref "RZ3") (pin "2") (pinfunction "2_2") (pintype "passive"))
      (node (ref "XA4") (pin "P41") (pinfunction "P41-AP4_GP52/LED1_RED_P41") (pintype "bidirectional"))
    )
    (net (code "14") (name "AP4_LED2_RED") (class "Default")
      (node (ref "R4") (pin "2") (pinfunction "2_2") (pintype "passive"))
      (node (ref "RZ6") (pin "2") (pinfunction "2_2") (pintype "passive"))
      (node (ref "XA4") (pin "P22") (pinfunction "P22-AP4_GP76/TT_LED2_RED_P22") (pintype "bidirectional"))
    )
    (net (code "15") (name "AP4_LED2_YELLOW") (class "Default")
      (node (ref "R3") (pin "2") (pinfunction "2_2") (pintype "passive"))
      (node (ref "RZ7") (pin "2") (pinfunction "2_2") (pintype "passive"))
      (node (ref "XA4") (pin "P32") (pinfunction "P32-AP4_GP88/TT_LED2_YELLOW_P32") (pintype "bidirectional"))
    )
    (net (code "16") (name "BATIN") (class "Default")
      (node (ref "C27") (pin "1") (pinfunction "1_1") (pintype "bidirectional"))
      (node (ref "R30") (pin "2") (pinfunction "2_2") (pintype "passive"))
      (node (ref "R31") (pin "1") (pinfunction "1_1") (pintype "passive"))
      (node (ref "XA4") (pin "P4") (pinfunction "P4-AP4_GP18/TT_BATIN_P4") (pintype "bidirectional"))
    )
    (net (code "17") (name "BATT_THERM") (class "Default")
      (node (ref "J4") (pin "2") (pinfunction "2_2") (pintype "bidirectional"))
      (node (ref "J4") (pin "2SUPP") (pinfunction "2_2SUPP") (pintype "bidirectional"))
      (node (ref "JP2") (pin "3") (pinfunction "3_3") (pintype "passive"))
    )
    (net (code "18") (name "BATT_TS") (class "Default")
      (node (ref "JP2") (pin "2") (pinfunction "2_2") (pintype "passive"))
      (node (ref "U3") (pin "9") (pinfunction "TS_9") (pintype "bidirectional"))
    )
    (net (code "19") (name "BUZZER_GATE") (class "Default")
      (node (ref "Q2") (pin "G") (pinfunction "G_G") (pintype "passive"))
      (node (ref "R25") (pin "1") (pinfunction "1_1") (pintype "passive"))
      (node (ref "XA4") (pin "P33") (pinfunction "P33-AP4_GP54/TT_BUZZER_GATE_P33") (pintype "bidirectional"))
    )
    (net (code "20") (name "DWM1_IRQ") (class "Default")
      (node (ref "R24") (pin "2") (pinfunction "2_2") (pintype "passive"))
      (node (ref "XA1") (pin "22") (pinfunction "IRQ/GP8_22") (pintype "bidirectional"))
      (node (ref "XA4") (pin "P35") (pinfunction "P35-AP4_GP27/TT_DW_IRQ_P35") (pintype "bidirectional"))
    )
    (net (code "21") (name "DWM1_WAKEUP") (class "Default")
      (node (ref "XA1") (pin "2") (pinfunction "WAKEUP_2") (pintype "input"))
      (node (ref "XA4") (pin "P34") (pinfunction "P34-AP4_GP26/TT_DW_WAKEUP_P34") (pintype "bidirectional"))
    )
    (net (code "22") (name "DWM2_IRQ") (class "Default")
      (node (ref "R1") (pin "2") (pinfunction "2_2") (pintype "passive"))
      (node (ref "RZ4") (pin "1") (pinfunction "1_1") (pintype "passive"))
      (node (ref "XA2") (pin "22") (pinfunction "IRQ/GP8_22") (pintype "bidirectional"))
    )
    (net (code "23") (name "DWM2_WAKEUP") (class "Default")
      (node (ref "RZ3") (pin "1") (pinfunction "1_1") (pintype "passive"))
      (node (ref "XA2") (pin "2") (pinfunction "WAKEUP_2") (pintype "input"))
    )
    (net (code "24") (name "DWM3_IRQ") (class "Default")
      (node (ref "R10") (pin "2") (pinfunction "2_2") (pintype "passive"))
      (node (ref "RZ6") (pin "1") (pinfunction "1_1") (pintype "passive"))
      (node (ref "XA3") (pin "22") (pinfunction "IRQ/GP8_22") (pintype "bidirectional"))
    )
    (net (code "25") (name "DWM3_WAKEUP") (class "Default")
      (node (ref "RZ7") (pin "1") (pinfunction "1_1") (pintype "passive"))
      (node (ref "XA3") (pin "2") (pinfunction "WAKEUP_2") (pintype "input"))
    )
    (net (code "26") (name "DW_SPI_CIPO") (class "Default")
      (node (ref "XA1") (pin "19") (pinfunction "SPI_MISO_19") (pintype "output"))
      (node (ref "XA2") (pin "19") (pinfunction "SPI_MISO_19") (pintype "output"))
      (node (ref "XA3") (pin "19") (pinfunction "SPI_MISO_19") (pintype "output"))
      (node (ref "XA4") (pin "P10") (pinfunction "P10-AP4_GP33/TT_DW_SPI_IO1_P10") (pintype "bidirectional"))
    )
    (net (code "27") (name "DW_SPI_CLK") (class "Default")
      (node (ref "XA1") (pin "20") (pinfunction "SPI_CLK_20") (pintype "input"))
      (node (ref "XA2") (pin "20") (pinfunction "SPI_CLK_20") (pintype "input"))
      (node (ref "XA3") (pin "20") (pinfunction "SPI_CLK_20") (pintype "input"))
      (node (ref "XA4") (pin "P12") (pinfunction "P12-AP4_GP31/TT_DW_SPI_CLK_P12") (pintype "bidirectional"))
    )
    (net (code "28") (name "DW_SPI_COPI") (class "Default")
      (node (ref "XA1") (pin "18") (pinfunction "SPI_MOSI_18") (pintype "input"))
      (node (ref "XA2") (pin "18") (pinfunction "SPI_MOSI_18") (pintype "input"))
      (node (ref "XA3") (pin "18") (pinfunction "SPI_MOSI_18") (pintype "input"))
      (node (ref "XA4") (pin "P11") (pinfunction "P11-AP4_GP32/TT_DW_SPI_IO0_P11") (pintype "bidirectional"))
    )
    (net (code "29") (name "FLASH_CLK") (class "Default")
      (node (ref "U5") (pin "6") (pinfunction "CLK_6") (pintype "input"))
      (node (ref "XA4") (pin "P7") (pinfunction "P7-AP4_GP47/TT_FLASH_SCK_P7") (pintype "bidirectional"))
    )
    (net (code "30") (name "FLASH_PDI-IO0") (class "Default")
      (node (ref "U5") (pin "5") (pinfunction "DI_5") (pintype "bidirectional"))
      (node (ref "XA4") (pin "P6") (pinfunction "P6-AP4_GP48/TT_FLASH_MOSI_P6") (pintype "bidirectional"))
    )
    (net (code "31") (name "FLASH_PDO-IO1") (class "Default")
      (node (ref "U5") (pin "2") (pinfunction "DO_2") (pintype "bidirectional"))
      (node (ref "XA4") (pin "P5") (pinfunction "P5-AP4_GP49/TT_FLASH_MISO_P5") (pintype "bidirectional"))
    )
    (net (code "32") (name "FLASH_~{CS}") (class "Default")
      (node (ref "R21") (pin "1") (pinfunction "1_1") (pintype "passive"))
      (node (ref "U5") (pin "1") (pinfunction "~{CS}_1") (pintype "input"))
      (node (ref "XA4") (pin "P42") (pinfunction "P42-AP4_GP69/TT_FLASH_~{CS}_P42") (pintype "bidirectional"))
    )
    (net (code "33") (name "FLASH_~{HOLD}-IO3") (class "Default")
      (node (ref "U5") (pin "7") (pinfunction "~{HOLD}_7") (pintype "bidirectional"))
      (node (ref "XA4") (pin "P24") (pinfunction "P24-AP4_GP06/TT_FLASH_~{HOLD}_P24") (pintype "bidirectional"))
    )
    (net (code "34") (name "FLASH_~{WP}-IO2") (class "Default")
      (node (ref "U5") (pin "3") (pinfunction "~{WP}_3") (pintype "bidirectional"))
      (node (ref "XA4") (pin "P23") (pinfunction "P23-AP4_GP30/TT_FLASH_~{WP}_P23") (pintype "bidirectional"))
    )
    (net (code "35") (name "GND") (class "Default")
      (node (ref "C27") (pin "2") (pinfunction "2_2") (pintype "bidirectional"))
      (node (ref "C28") (pin "2") (pinfunction "2_2") (pintype "bidirectional"))
      (node (ref "C29") (pin "2") (pinfunction "2_2") (pintype "bidirectional"))
      (node (ref "C30") (pin "2") (pinfunction "2_2") (pintype "bidirectional"))
      (node (ref "C31") (pin "2") (pinfunction "2_2") (pintype "bidirectional"))
      (node (ref "C32") (pin "2") (pinfunction "2_2") (pintype "bidirectional"))
      (node (ref "C35") (pin "2") (pinfunction "2_2") (pintype "bidirectional"))
      (node (ref "C41") (pin "2") (pinfunction "2_2") (pintype "bidirectional"))
      (node (ref "C42") (pin "2") (pinfunction "2_2") (pintype "bidirectional"))
      (node (ref "C43") (pin "2") (pinfunction "2_2") (pintype "bidirectional"))
      (node (ref "C44") (pin "2") (pinfunction "2_2") (pintype "bidirectional"))
      (node (ref "C45") (pin "1") (pinfunction "1_1") (pintype "bidirectional"))
      (node (ref "C46") (pin "2") (pinfunction "2_2") (pintype "bidirectional"))
      (node (ref "C47") (pin "1") (pinfunction "1_1") (pintype "bidirectional"))
      (node (ref "C48") (pin "2") (pinfunction "2_2") (pintype "bidirectional"))
      (node (ref "C5") (pin "P$1") (pinfunction "1_P$1") (pintype "bidirectional"))
      (node (ref "C53") (pin "2") (pinfunction "2_2") (pintype "bidirectional"))
      (node (ref "C56") (pin "2") (pinfunction "2_2") (pintype "bidirectional"))
      (node (ref "C57") (pin "2") (pinfunction "2_2") (pintype "bidirectional"))
      (node (ref "C6") (pin "P$1") (pinfunction "1_P$1") (pintype "bidirectional"))
      (node (ref "J1") (pin "5") (pinfunction "GND_5") (pintype "bidirectional"))
      (node (ref "J4") (pin "1") (pinfunction "1_1") (pintype "bidirectional"))
      (node (ref "J4") (pin "1SUPP") (pinfunction "1_1SUPP") (pintype "bidirectional"))
      (node (ref "JP6") (pin "1") (pinfunction "1_1") (pintype "passive"))
      (node (ref "JP9") (pin "2") (pinfunction "2_2") (pintype "passive"))
      (node (ref "Q2") (pin "S") (pinfunction "S_S") (pintype "passive"))
      (node (ref "R1") (pin "1") (pinfunction "1_1") (pintype "passive"))
      (node (ref "R10") (pin "1") (pinfunction "1_1") (pintype "passive"))
      (node (ref "R14") (pin "1") (pinfunction "1_1") (pintype "passive"))
      (node (ref "R15") (pin "1") (pinfunction "1_1") (pintype "passive"))
      (node (ref "R24") (pin "1") (pinfunction "1_1") (pintype "passive"))
      (node (ref "R25") (pin "2") (pinfunction "2_2") (pintype "passive"))
      (node (ref "R26") (pin "1") (pinfunction "1_1") (pintype "passive"))
      (node (ref "R27") (pin "1") (pinfunction "1_1") (pintype "passive"))
      (node (ref "R30") (pin "1") (pinfunction "1_1") (pintype "passive"))
      (node (ref "R6") (pin "2") (pinfunction "2_2") (pintype "passive"))
      (node (ref "RX7") (pin "1") (pinfunction "1_1") (pintype "passive"))
      (node (ref "U3") (pin "3") (pinfunction "VSS_3") (pintype "bidirectional"))
      (node (ref "U3") (pin "7") (pinfunction "ISET2_7") (pintype "bidirectional"))
      (node (ref "U3") (pin "PAD") (pinfunction "VSS_PAD") (pintype "bidirectional"))
      (node (ref "U4") (pin "1") (pinfunction "PGND_1") (pintype "bidirectional"))
      (node (ref "U4") (pin "10") (pinfunction "EN1_10") (pintype "bidirectional"))
      (node (ref "U4") (pin "11") (pinfunction "EN2_11") (pintype "bidirectional"))
      (node (ref "U4") (pin "20") (pinfunction "PGND_20") (pintype "bidirectional"))
      (node (ref "U4") (pin "9") (pinfunction "AD_9") (pintype "bidirectional"))
      (node (ref "U4") (pin "PAD") (pinfunction "PGND_PAD") (pintype "bidirectional"))
      (node (ref "U5") (pin "4") (pinfunction "GND_4") (pintype "bidirectional"))
      (node (ref "U6") (pin "18") (pinfunction "COM2_18") (pintype "bidirectional"))
      (node (ref "U6") (pin "2") (pinfunction "GND_2") (pintype "bidirectional"))
      (node (ref "U6") (pin "25") (pinfunction "GNDIO_25") (pintype "bidirectional"))
      (node (ref "U6") (pin "5") (pinfunction "PS1_5") (pintype "input"))
      (node (ref "U6") (pin "6") (pinfunction "PS0_6") (pintype "input"))
      (node (ref "VR1") (pin "13") (pinfunction "GND2_13") (pintype "bidirectional"))
      (node (ref "VR1") (pin "3") (pinfunction "GND2_3") (pintype "bidirectional"))
      (node (ref "VR1") (pin "9") (pinfunction "GND1_9") (pintype "bidirectional"))
      (node (ref "XA1") (pin "16") (pinfunction "VSS_16") (pintype "bidirectional"))
      (node (ref "XA1") (pin "21") (pinfunction "VSS_21") (pintype "bidirectional"))
      (node (ref "XA1") (pin "23") (pinfunction "VSS_23") (pintype "bidirectional"))
      (node (ref "XA1") (pin "24") (pinfunction "VSS_24") (pintype "bidirectional"))
      (node (ref "XA1") (pin "8") (pinfunction "VSS_8") (pintype "bidirectional"))
      (node (ref "XA2") (pin "16") (pinfunction "VSS_16") (pintype "bidirectional"))
      (node (ref "XA2") (pin "21") (pinfunction "VSS_21") (pintype "bidirectional"))
      (node (ref "XA2") (pin "23") (pinfunction "VSS_23") (pintype "bidirectional"))
      (node (ref "XA2") (pin "24") (pinfunction "VSS_24") (pintype "bidirectional"))
      (node (ref "XA2") (pin "8") (pinfunction "VSS_8") (pintype "bidirectional"))
      (node (ref "XA3") (pin "16") (pinfunction "VSS_16") (pintype "bidirectional"))
      (node (ref "XA3") (pin "21") (pinfunction "VSS_21") (pintype "bidirectional"))
      (node (ref "XA3") (pin "23") (pinfunction "VSS_23") (pintype "bidirectional"))
      (node (ref "XA3") (pin "24") (pinfunction "VSS_24") (pintype "bidirectional"))
      (node (ref "XA3") (pin "8") (pinfunction "VSS_8") (pintype "bidirectional"))
      (node (ref "XA4") (pin "P13") (pinfunction "P13-GND_P13") (pintype "bidirectional"))
      (node (ref "XA4") (pin "P37") (pinfunction "P37-GND_P37") (pintype "bidirectional"))
      (node (ref "XR19") (pin "1") (pinfunction "1_1") (pintype "passive"))
    )
    (net (code "36") (name "Net-(A4-ANTENNA)") (class "Default")
      (node (ref "A4") (pin "S1") (pinfunction "ANTENNA_S1") (pintype "bidirectional"))
      (node (ref "C1") (pin "1") (pinfunction "1_1") (pintype "bidirectional"))
      (node (ref "L3") (pin "1") (pinfunction "1_1") (pintype "bidirectional"))
    )
    (net (code "37") (name "Net-(C5-2)") (class "Default")
      (node (ref "C5") (pin "P$2") (pinfunction "2_P$2") (pintype "bidirectional"))
      (node (ref "U6") (pin "27") (pinfunction "XIN32_27") (pintype "bidirectional"))
      (node (ref "X2") (pin "2") (pinfunction "2_2") (pintype "bidirectional"))
    )
    (net (code "38") (name "Net-(C6-2)") (class "Default")
      (node (ref "C6") (pin "P$2") (pinfunction "2_P$2") (pintype "bidirectional"))
      (node (ref "U6") (pin "26") (pinfunction "XOUT32_26") (pintype "bidirectional"))
      (node (ref "X2") (pin "1") (pinfunction "1_1") (pintype "bidirectional"))
    )
    (net (code "39") (name "Net-(C7-2)") (class "Default")
      (node (ref "C7") (pin "P$2") (pinfunction "2_P$2") (pintype "bidirectional"))
      (node (ref "R26") (pin "2") (pinfunction "2_2") (pintype "passive"))
      (node (ref "R28") (pin "1") (pinfunction "1_1") (pintype "passive"))
      (node (ref "VR1") (pin "10") (pinfunction "FB2_10") (pintype "bidirectional"))
    )
    (net (code "40") (name "Net-(C8-1)") (class "Default")
      (node (ref "C8") (pin "P$1") (pinfunction "1_P$1") (pintype "bidirectional"))
      (node (ref "R27") (pin "2") (pinfunction "2_2") (pintype "passive"))
      (node (ref "R29") (pin "2") (pinfunction "2_2") (pintype "passive"))
      (node (ref "VR1") (pin "4") (pinfunction "FB1_4") (pintype "bidirectional"))
    )
    (net (code "41") (name "Net-(D1-PadA1)") (class "Default")
      (node (ref "D1") (pin "A1") (pinfunction "A1_A1") (pintype "bidirectional"))
      (node (ref "D1") (pin "A2") (pinfunction "A2_A2") (pintype "bidirectional"))
      (node (ref "D2") (pin "A1") (pinfunction "A1_A1") (pintype "bidirectional"))
      (node (ref "D2") (pin "A2") (pinfunction "A2_A2") (pintype "bidirectional"))
      (node (ref "RZ1") (pin "1") (pinfunction "1_1") (pintype "passive"))
    )
    (net (code "42") (name "Net-(D1-PadC1)") (class "Default")
      (node (ref "D1") (pin "C1") (pinfunction "C1_C1") (pintype "bidirectional"))
      (node (ref "R5") (pin "1") (pinfunction "1_1") (pintype "passive"))
    )
    (net (code "43") (name "Net-(D1-PadC2)") (class "Default")
      (node (ref "D1") (pin "C2") (pinfunction "C2_C2") (pintype "bidirectional"))
      (node (ref "R2") (pin "1") (pinfunction "1_1") (pintype "passive"))
    )
    (net (code "44") (name "Net-(D2-PadC1)") (class "Default")
      (node (ref "D2") (pin "C1") (pinfunction "C1_C1") (pintype "bidirectional"))
      (node (ref "R4") (pin "1") (pinfunction "1_1") (pintype "passive"))
    )
    (net (code "45") (name "Net-(D2-PadC2)") (class "Default")
      (node (ref "D2") (pin "C2") (pinfunction "C2_C2") (pintype "bidirectional"))
      (node (ref "R3") (pin "1") (pinfunction "1_1") (pintype "passive"))
    )
    (net (code "46") (name "Net-(JP2-Pad1)") (class "Default")
      (node (ref "JP2") (pin "1") (pinfunction "1_1") (pintype "passive"))
      (node (ref "XR19") (pin "2") (pinfunction "2_2") (pintype "passive"))
    )
    (net (code "47") (name "Net-(L1-1)") (class "Default")
      (node (ref "L1") (pin "P$1") (pinfunction "1_P$1") (pintype "bidirectional"))
      (node (ref "VR1") (pin "2") (pinfunction "LX2_2") (pintype "bidirectional"))
    )
    (net (code "48") (name "Net-(L2-2)") (class "Default")
      (node (ref "L2") (pin "P$2") (pinfunction "2_P$2") (pintype "bidirectional"))
      (node (ref "VR1") (pin "8") (pinfunction "LX1_8") (pintype "bidirectional"))
    )
    (net (code "49") (name "Net-(L4-1)") (class "Default")
      (node (ref "C17") (pin "2") (pinfunction "2_2") (pintype "bidirectional"))
      (node (ref "C18") (pin "2") (pinfunction "2_2") (pintype "bidirectional"))
      (node (ref "C19") (pin "2") (pinfunction "2_2") (pintype "bidirectional"))
      (node (ref "L4") (pin "P$1") (pinfunction "1_P$1") (pintype "bidirectional"))
    )
    (net (code "50") (name "Net-(L4-2)") (class "Default")
      (node (ref "C10") (pin "2") (pinfunction "2_2") (pintype "bidirectional"))
      (node (ref "C16") (pin "2") (pinfunction "2_2") (pintype "bidirectional"))
      (node (ref "C21") (pin "2") (pinfunction "2_2") (pintype "bidirectional"))
      (node (ref "C39") (pin "2") (pinfunction "2_2") (pintype "bidirectional"))
      (node (ref "C9") (pin "2") (pinfunction "2_2") (pintype "bidirectional"))
      (node (ref "L4") (pin "P$2") (pinfunction "2_P$2") (pintype "bidirectional"))
      (node (ref "U4") (pin "19") (pinfunction "AC2_19") (pintype "bidirectional"))
    )
    (net (code "51") (name "Net-(LS1-N)") (class "Default")
      (node (ref "D4") (pin "ANODE") (pinfunction "ANODE_ANODE") (pintype "bidirectional"))
      (node (ref "LS1") (pin "-") (pinfunction "N_-") (pintype "passive"))
      (node (ref "Q2") (pin "D") (pinfunction "D_D") (pintype "passive"))
    )
    (net (code "52") (name "Net-(LS1-P)") (class "Default")
      (node (ref "C44") (pin "1") (pinfunction "1_1") (pintype "bidirectional"))
      (node (ref "D4") (pin "CATHODE") (pinfunction "CATHODE_CATHODE") (pintype "bidirectional"))
      (node (ref "JP8") (pin "2") (pinfunction "2_2") (pintype "passive"))
      (node (ref "LS1") (pin "+") (pinfunction "P_+") (pintype "passive"))
    )
    (net (code "53") (name "Net-(R6-Pad1)") (class "Default")
      (node (ref "R6") (pin "1") (pinfunction "1_1") (pintype "passive"))
      (node (ref "R7") (pin "2") (pinfunction "2_2") (pintype "passive"))
    )
    (net (code "54") (name "Net-(R8-Pad2)") (class "Default")
      (node (ref "R8") (pin "2") (pinfunction "2_2") (pintype "passive"))
      (node (ref "R9") (pin "1") (pinfunction "1_1") (pintype "passive"))
    )
    (net (code "55") (name "Net-(R13-Pad1)") (class "Default")
      (node (ref "R13") (pin "1") (pinfunction "1_1") (pintype "passive"))
      (node (ref "R14") (pin "2") (pinfunction "2_2") (pintype "passive"))
    )
    (net (code "56") (name "Net-(R13-Pad2)") (class "Default")
      (node (ref "R13") (pin "2") (pinfunction "2_2") (pintype "passive"))
      (node (ref "RT1") (pin "1") (pinfunction "1_1") (pintype "passive"))
    )
    (net (code "57") (name "Net-(R18-Pad2)") (class "Default")
      (node (ref "R18") (pin "2") (pinfunction "2_2") (pintype "passive"))
      (node (ref "R23") (pin "1") (pinfunction "1_1") (pintype "passive"))
    )
    (net (code "58") (name "Net-(U3-ISET)") (class "Default")
      (node (ref "R15") (pin "2") (pinfunction "2_2") (pintype "passive"))
      (node (ref "U3") (pin "2") (pinfunction "ISET_2") (pintype "bidirectional"))
    )
    (net (code "59") (name "Net-(U3-PRETERM)") (class "Default")
      (node (ref "RX7") (pin "2") (pinfunction "2_2") (pintype "passive"))
      (node (ref "U3") (pin "4") (pinfunction "PRETERM_4") (pintype "bidirectional"))
    )
    (net (code "60") (name "Net-(U4-AC1)") (class "Default")
      (node (ref "C10") (pin "1") (pinfunction "1_1") (pintype "bidirectional"))
      (node (ref "C15") (pin "2") (pinfunction "2_2") (pintype "bidirectional"))
      (node (ref "C17") (pin "1") (pinfunction "1_1") (pintype "bidirectional"))
      (node (ref "C18") (pin "1") (pinfunction "1_1") (pintype "bidirectional"))
      (node (ref "C19") (pin "1") (pinfunction "1_1") (pintype "bidirectional"))
      (node (ref "C20") (pin "2") (pinfunction "2_2") (pintype "bidirectional"))
      (node (ref "C38") (pin "2") (pinfunction "2_2") (pintype "bidirectional"))
      (node (ref "C9") (pin "1") (pinfunction "1_1") (pintype "bidirectional"))
      (node (ref "U4") (pin "2") (pinfunction "AC1_2") (pintype "bidirectional"))
    )
    (net (code "61") (name "Net-(U4-BOOT1)") (class "Default")
      (node (ref "C15") (pin "1") (pinfunction "1_1") (pintype "bidirectional"))
      (node (ref "U4") (pin "3") (pinfunction "BOOT1_3") (pintype "bidirectional"))
    )
    (net (code "62") (name "Net-(U4-BOOT2)") (class "Default")
      (node (ref "C16") (pin "1") (pinfunction "1_1") (pintype "bidirectional"))
      (node (ref "U4") (pin "17") (pinfunction "BOOT2_17") (pintype "bidirectional"))
    )
    (net (code "63") (name "Net-(U4-CLAMP1)") (class "Default")
      (node (ref "C38") (pin "1") (pinfunction "1_1") (pintype "bidirectional"))
      (node (ref "U4") (pin "5") (pinfunction "CLAMP1_5") (pintype "bidirectional"))
    )
    (net (code "64") (name "Net-(U4-CLAMP2)") (class "Default")
      (node (ref "C39") (pin "1") (pinfunction "1_1") (pintype "bidirectional"))
      (node (ref "U4") (pin "16") (pinfunction "CLAMP2_16") (pintype "bidirectional"))
    )
    (net (code "65") (name "Net-(U4-COMM1)") (class "Default")
      (node (ref "C20") (pin "1") (pinfunction "1_1") (pintype "bidirectional"))
      (node (ref "U4") (pin "6") (pinfunction "COMM1_6") (pintype "bidirectional"))
    )
    (net (code "66") (name "Net-(U4-COMM2)") (class "Default")
      (node (ref "C21") (pin "1") (pinfunction "1_1") (pintype "bidirectional"))
      (node (ref "U4") (pin "15") (pinfunction "COMM2_15") (pintype "bidirectional"))
    )
    (net (code "67") (name "Net-(U4-FOD)") (class "Default")
      (node (ref "R23") (pin "2") (pinfunction "2_2") (pintype "passive"))
      (node (ref "R7") (pin "1") (pinfunction "1_1") (pintype "passive"))
      (node (ref "R9") (pin "2") (pinfunction "2_2") (pintype "passive"))
      (node (ref "U4") (pin "14") (pinfunction "FOD_14") (pintype "bidirectional"))
    )
    (net (code "68") (name "Net-(U4-ILIM)") (class "Default")
      (node (ref "R8") (pin "1") (pinfunction "1_1") (pintype "passive"))
      (node (ref "U4") (pin "12") (pinfunction "ILIM_12") (pintype "bidirectional"))
    )
    (net (code "69") (name "Net-(U4-RECT)") (class "Default")
      (node (ref "C28") (pin "1") (pinfunction "1_1") (pintype "bidirectional"))
      (node (ref "C56") (pin "1") (pinfunction "1_1") (pintype "bidirectional"))
      (node (ref "C57") (pin "1") (pinfunction "1_1") (pintype "bidirectional"))
      (node (ref "R18") (pin "1") (pinfunction "1_1") (pintype "passive"))
      (node (ref "U4") (pin "18") (pinfunction "RECT_18") (pintype "bidirectional"))
    )
    (net (code "70") (name "Net-(U6-CAP)") (class "Default")
      (node (ref "C43") (pin "1") (pinfunction "1_1") (pintype "bidirectional"))
      (node (ref "U6") (pin "9") (pinfunction "CAP_9") (pintype "bidirectional"))
    )
    (net (code "71") (name "Net-(U6-COM3)") (class "Default")
      (node (ref "JP6") (pin "2") (pinfunction "2_2") (pintype "passive"))
      (node (ref "U6") (pin "17") (pinfunction "COM3_17") (pintype "bidirectional"))
    )
    (net (code "72") (name "Net-(XA4-P15-BLE_RFOUT)") (class "Default")
      (node (ref "C2") (pin "1") (pinfunction "1_1") (pintype "bidirectional"))
      (node (ref "L3") (pin "2") (pinfunction "2_2") (pintype "bidirectional"))
      (node (ref "XA4") (pin "P15") (pinfunction "P15-BLE_RFOUT_P15") (pintype "bidirectional"))
    )
    (net (code "73") (name "QI_TS_CTRL") (class "Default")
      (node (ref "C30") (pin "1") (pinfunction "1_1") (pintype "bidirectional"))
      (node (ref "RT1") (pin "2") (pinfunction "2_2") (pintype "passive"))
      (node (ref "U4") (pin "13") (pinfunction "TS/CTRL_13") (pintype "bidirectional"))
      (node (ref "XA4") (pin "P44") (pinfunction "P44-AP4_GP66/TT_QI_TS_CTRL_P44") (pintype "bidirectional"))
    )
    (net (code "74") (name "VBAT") (class "Default")
      (node (ref "C42") (pin "1") (pinfunction "1_1") (pintype "bidirectional"))
      (node (ref "J4") (pin "3") (pinfunction "3_3") (pintype "bidirectional"))
      (node (ref "J4") (pin "3SUPP") (pinfunction "3_3SUPP") (pintype "bidirectional"))
      (node (ref "JP9") (pin "1") (pinfunction "1_1") (pintype "passive"))
      (node (ref "S1") (pin "2") (pinfunction "2_2") (pintype "passive"))
      (node (ref "U3") (pin "10") (pinfunction "OUT_10") (pintype "bidirectional"))
    )
    (net (code "75") (name "VBAT_SWITCHED") (class "Default")
      (node (ref "C45") (pin "2") (pinfunction "2_2") (pintype "bidirectional"))
      (node (ref "C48") (pin "1") (pinfunction "1_1") (pintype "bidirectional"))
      (node (ref "JP8") (pin "1") (pinfunction "1_1") (pintype "passive"))
      (node (ref "R31") (pin "2") (pinfunction "2_2") (pintype "passive"))
      (node (ref "S1") (pin "3") (pinfunction "3_3") (pintype "passive"))
      (node (ref "VR1") (pin "1") (pinfunction "VIN2_1") (pintype "bidirectional"))
      (node (ref "VR1") (pin "12") (pinfunction "EN2_12") (pintype "bidirectional"))
      (node (ref "VR1") (pin "6") (pinfunction "EN1_6") (pintype "bidirectional"))
      (node (ref "VR1") (pin "7") (pinfunction "VIN1_7") (pintype "bidirectional"))
    )
    (net (code "76") (name "VQI") (class "Default")
      (node (ref "C29") (pin "1") (pinfunction "1_1") (pintype "bidirectional"))
      (node (ref "C41") (pin "1") (pinfunction "1_1") (pintype "bidirectional"))
      (node (ref "C53") (pin "1") (pinfunction "1_1") (pintype "bidirectional"))
      (node (ref "U3") (pin "1") (pinfunction "IN_1") (pintype "bidirectional"))
      (node (ref "U4") (pin "4") (pinfunction "OUT_4") (pintype "bidirectional"))
    )
    (net (code "77") (name "unconnected-(J1-SWO-Pad6)") (class "Default")
      (node (ref "J1") (pin "6") (pinfunction "SWO_6") (pintype "bidirectional"))
    )
    (net (code "78") (name "unconnected-(S1-Pad1)") (class "Default")
      (node (ref "S1") (pin "1") (pinfunction "1_1") (pintype "passive"))
    )
    (net (code "79") (name "unconnected-(U4-~{AD-EN}-Pad8)") (class "Default")
      (node (ref "U4") (pin "8") (pinfunction "~{AD-EN}_8") (pintype "bidirectional"))
    )
    (net (code "80") (name "unconnected-(VR1-NC1-Pad5)") (class "Default")
      (node (ref "VR1") (pin "5") (pinfunction "NC1_5") (pintype "bidirectional"))
    )
    (net (code "81") (name "unconnected-(VR1-NC2-Pad11)") (class "Default")
      (node (ref "VR1") (pin "11") (pinfunction "NC2_11") (pintype "bidirectional"))
    )
    (net (code "82") (name "unconnected-(XA1-EXTON-Pad1)") (class "Default")
      (node (ref "XA1") (pin "1") (pinfunction "EXTON_1") (pintype "output"))
    )
    (net (code "83") (name "unconnected-(XA1-GP4-Pad11)") (class "Default")
      (node (ref "XA1") (pin "11") (pinfunction "GP4_11") (pintype "bidirectional"))
    )
    (net (code "84") (name "unconnected-(XA1-RXLED{slash}GP2-Pad13)") (class "Default")
      (node (ref "XA1") (pin "13") (pinfunction "RXLED/GP2_13") (pintype "bidirectional"))
    )
    (net (code "85") (name "unconnected-(XA1-RXOKLED{slash}GP0-Pad15)") (class "Default")
      (node (ref "XA1") (pin "15") (pinfunction "RXOKLED/GP0_15") (pintype "bidirectional"))
    )
    (net (code "86") (name "unconnected-(XA1-SFDLED{slash}GP1-Pad14)") (class "Default")
      (node (ref "XA1") (pin "14") (pinfunction "SFDLED/GP1_14") (pintype "bidirectional"))
    )
    (net (code "87") (name "unconnected-(XA1-SPI_PHA{slash}GP6-Pad9)") (class "Default")
      (node (ref "XA1") (pin "9") (pinfunction "SPI_PHA/GP6_9") (pintype "bidirectional"))
    )
    (net (code "88") (name "unconnected-(XA1-SPI_POL{slash}GP5-Pad10)") (class "Default")
      (node (ref "XA1") (pin "10") (pinfunction "SPI_POL/GP5_10") (pintype "bidirectional"))
    )
    (net (code "89") (name "unconnected-(XA1-SYNC{slash}GP7-Pad4)") (class "Default")
      (node (ref "XA1") (pin "4") (pinfunction "SYNC/GP7_4") (pintype "bidirectional"))
    )
    (net (code "90") (name "unconnected-(XA1-TXLED{slash}GP3-Pad12)") (class "Default")
      (node (ref "XA1") (pin "12") (pinfunction "TXLED/GP3_12") (pintype "bidirectional"))
    )
    (net (code "91") (name "unconnected-(XA2-EXTON-Pad1)") (class "Default")
      (node (ref "XA2") (pin "1") (pinfunction "EXTON_1") (pintype "output"))
    )
    (net (code "92") (name "unconnected-(XA2-GP4-Pad11)") (class "Default")
      (node (ref "XA2") (pin "11") (pinfunction "GP4_11") (pintype "bidirectional"))
    )
    (net (code "93") (name "unconnected-(XA2-RXLED{slash}GP2-Pad13)") (class "Default")
      (node (ref "XA2") (pin "13") (pinfunction "RXLED/GP2_13") (pintype "bidirectional"))
    )
    (net (code "94") (name "unconnected-(XA2-RXOKLED{slash}GP0-Pad15)") (class "Default")
      (node (ref "XA2") (pin "15") (pinfunction "RXOKLED/GP0_15") (pintype "bidirectional"))
    )
    (net (code "95") (name "unconnected-(XA2-SFDLED{slash}GP1-Pad14)") (class "Default")
      (node (ref "XA2") (pin "14") (pinfunction "SFDLED/GP1_14") (pintype "bidirectional"))
    )
    (net (code "96") (name "unconnected-(XA2-SPI_PHA{slash}GP6-Pad9)") (class "Default")
      (node (ref "XA2") (pin "9") (pinfunction "SPI_PHA/GP6_9") (pintype "bidirectional"))
    )
    (net (code "97") (name "unconnected-(XA2-SPI_POL{slash}GP5-Pad10)") (class "Default")
      (node (ref "XA2") (pin "10") (pinfunction "SPI_POL/GP5_10") (pintype "bidirectional"))
    )
    (net (code "98") (name "unconnected-(XA2-SYNC{slash}GP7-Pad4)") (class "Default")
      (node (ref "XA2") (pin "4") (pinfunction "SYNC/GP7_4") (pintype "bidirectional"))
    )
    (net (code "99") (name "unconnected-(XA2-TXLED{slash}GP3-Pad12)") (class "Default")
      (node (ref "XA2") (pin "12") (pinfunction "TXLED/GP3_12") (pintype "bidirectional"))
    )
    (net (code "100") (name "unconnected-(XA3-EXTON-Pad1)") (class "Default")
      (node (ref "XA3") (pin "1") (pinfunction "EXTON_1") (pintype "output"))
    )
    (net (code "101") (name "unconnected-(XA3-GP4-Pad11)") (class "Default")
      (node (ref "XA3") (pin "11") (pinfunction "GP4_11") (pintype "bidirectional"))
    )
    (net (code "102") (name "unconnected-(XA3-RXLED{slash}GP2-Pad13)") (class "Default")
      (node (ref "XA3") (pin "13") (pinfunction "RXLED/GP2_13") (pintype "bidirectional"))
    )
    (net (code "103") (name "unconnected-(XA3-RXOKLED{slash}GP0-Pad15)") (class "Default")
      (node (ref "XA3") (pin "15") (pinfunction "RXOKLED/GP0_15") (pintype "bidirectional"))
    )
    (net (code "104") (name "unconnected-(XA3-SFDLED{slash}GP1-Pad14)") (class "Default")
      (node (ref "XA3") (pin "14") (pinfunction "SFDLED/GP1_14") (pintype "bidirectional"))
    )
    (net (code "105") (name "unconnected-(XA3-SPI_PHA{slash}GP6-Pad9)") (class "Default")
      (node (ref "XA3") (pin "9") (pinfunction "SPI_PHA/GP6_9") (pintype "bidirectional"))
    )
    (net (code "106") (name "unconnected-(XA3-SPI_POL{slash}GP5-Pad10)") (class "Default")
      (node (ref "XA3") (pin "10") (pinfunction "SPI_POL/GP5_10") (pintype "bidirectional"))
    )
    (net (code "107") (name "unconnected-(XA3-SYNC{slash}GP7-Pad4)") (class "Default")
      (node (ref "XA3") (pin "4") (pinfunction "SYNC/GP7_4") (pintype "bidirectional"))
    )
    (net (code "108") (name "unconnected-(XA3-TXLED{slash}GP3-Pad12)") (class "Default")
      (node (ref "XA3") (pin "12") (pinfunction "TXLED/GP3_12") (pintype "bidirectional"))
    )
    (net (code "109") (name "unconnected-(XA4-P18-UNUSED-PadP18)") (class "Default")
      (node (ref "XA4") (pin "P18") (pinfunction "P18-UNUSED_P18") (pintype "bidirectional"))
    )
    (net (code "110") (name "unconnected-(XA4-P19-UNUSED-PadP19)") (class "Default")
      (node (ref "XA4") (pin "P19") (pinfunction "P19-UNUSED_P19") (pintype "bidirectional"))
    )
    (net (code "111") (name "unconnected-(XA4-P20-AP4_USB0_P-PadP20)") (class "Default")
      (node (ref "XA4") (pin "P20") (pinfunction "P20-AP4_USB0_P_P20") (pintype "bidirectional"))
    )
    (net (code "112") (name "unconnected-(XA4-P21-AP4_USB0_N-PadP21)") (class "Default")
      (node (ref "XA4") (pin "P21") (pinfunction "P21-AP4_USB0_N_P21") (pintype "bidirectional"))
    )
    (net (code "113") (name "unconnected-(XA4-P25-UNUSED-PadP25)") (class "Default")
      (node (ref "XA4") (pin "P25") (pinfunction "P25-UNUSED_P25") (pintype "bidirectional"))
    )
    (net (code "114") (name "unconnected-(XA4-P26-AP4_VDDUSB_0P9-PadP26)") (class "Default")
      (node (ref "XA4") (pin "P26") (pinfunction "P26-AP4_VDDUSB_0P9_P26") (pintype "bidirectional"))
    )
    (net (code "115") (name "unconnected-(XA4-P27-AP4-VDDUSB_3P3-PadP27)") (class "Default")
      (node (ref "XA4") (pin "P27") (pinfunction "P27-AP4-VDDUSB_3P3_P27") (pintype "bidirectional"))
    )
    (net (code "116") (name "unconnected-(XA4-P28_AP4_VDDMIPI_1P8-PadP28)") (class "Default")
      (node (ref "XA4") (pin "P28") (pinfunction "P28_AP4_VDDMIPI_1P8_P28") (pintype "bidirectional"))
    )
    (net (code "117") (name "unconnected-(XA4-P38-AP4_~{RESET}-PadP38)") (class "Default")
      (node (ref "XA4") (pin "P38") (pinfunction "P38-AP4_~{RESET}_P38") (pintype "bidirectional"))
    )
    (net (code "118") (name "unconnected-(XA4-P39-UNUSED-PadP39)") (class "Default")
      (node (ref "XA4") (pin "P39") (pinfunction "P39-UNUSED_P39") (pintype "bidirectional"))
    )
    (net (code "119") (name "~{CHG}") (class "Default")
      (node (ref "U3") (pin "8") (pinfunction "~{CHG}_8") (pintype "bidirectional"))
      (node (ref "U4") (pin "7") (pinfunction "~{CHG}_7") (pintype "bidirectional"))
      (node (ref "XA4") (pin "P2") (pinfunction "P2-AP4_GP58/TT_~{CHG}_P2") (pintype "bidirectional"))
    )
    (net (code "120") (name "~{DWM1_RST}") (class "Default")
      (node (ref "RZ2") (pin "2") (pinfunction "2_2") (pintype "passive"))
      (node (ref "RZ5") (pin "2") (pinfunction "2_2") (pintype "passive"))
      (node (ref "XA1") (pin "3") (pinfunction "~{RST}_3") (pintype "input"))
      (node (ref "XA4") (pin "P43") (pinfunction "P43-AP4_GP50/TT_~{DW_RESET}_P43") (pintype "bidirectional"))
    )
    (net (code "121") (name "~{DWM1_SPI_CS}") (class "Default")
      (node (ref "XA1") (pin "17") (pinfunction "~{SPI_CS}_17") (pintype "bidirectional"))
      (node (ref "XA4") (pin "P1") (pinfunction "P1-AP4_GP29/TT_~{DW_SPI_CS}_P1") (pintype "bidirectional"))
    )
    (net (code "122") (name "~{DWM2_RST}") (class "Default")
      (node (ref "RZ2") (pin "1") (pinfunction "1_1") (pintype "passive"))
      (node (ref "XA2") (pin "3") (pinfunction "~{RST}_3") (pintype "input"))
    )
    (net (code "123") (name "~{DWM2_SPI_CS}") (class "Default")
      (node (ref "XA2") (pin "17") (pinfunction "~{SPI_CS}_17") (pintype "bidirectional"))
      (node (ref "XA4") (pin "P8") (pinfunction "P8-AP4_GP24/TT_RFSW_V1_P8") (pintype "bidirectional"))
    )
    (net (code "124") (name "~{DWM3_RST}") (class "Default")
      (node (ref "RZ5") (pin "1") (pinfunction "1_1") (pintype "passive"))
      (node (ref "XA3") (pin "3") (pinfunction "~{RST}_3") (pintype "input"))
    )
    (net (code "125") (name "~{DWM3_SPI_CS}") (class "Default")
      (node (ref "XA3") (pin "17") (pinfunction "~{SPI_CS}_17") (pintype "bidirectional"))
      (node (ref "XA4") (pin "P9") (pinfunction "P9-AP4_GP25/TT_RFSW_V2_P9") (pintype "bidirectional"))
    )
    (net (code "126") (name "~{PG}") (class "Default")
      (node (ref "U3") (pin "5") (pinfunction "~{PG}_5") (pintype "bidirectional"))
      (node (ref "XA4") (pin "P3") (pinfunction "P3-AP4_GP60/TT_~{PG}_P3") (pintype "bidirectional"))
    )
  )
)
